# reaction_wheel_board_CURRENT.net
KiCad netlist of a schematic drawn in EAGLE
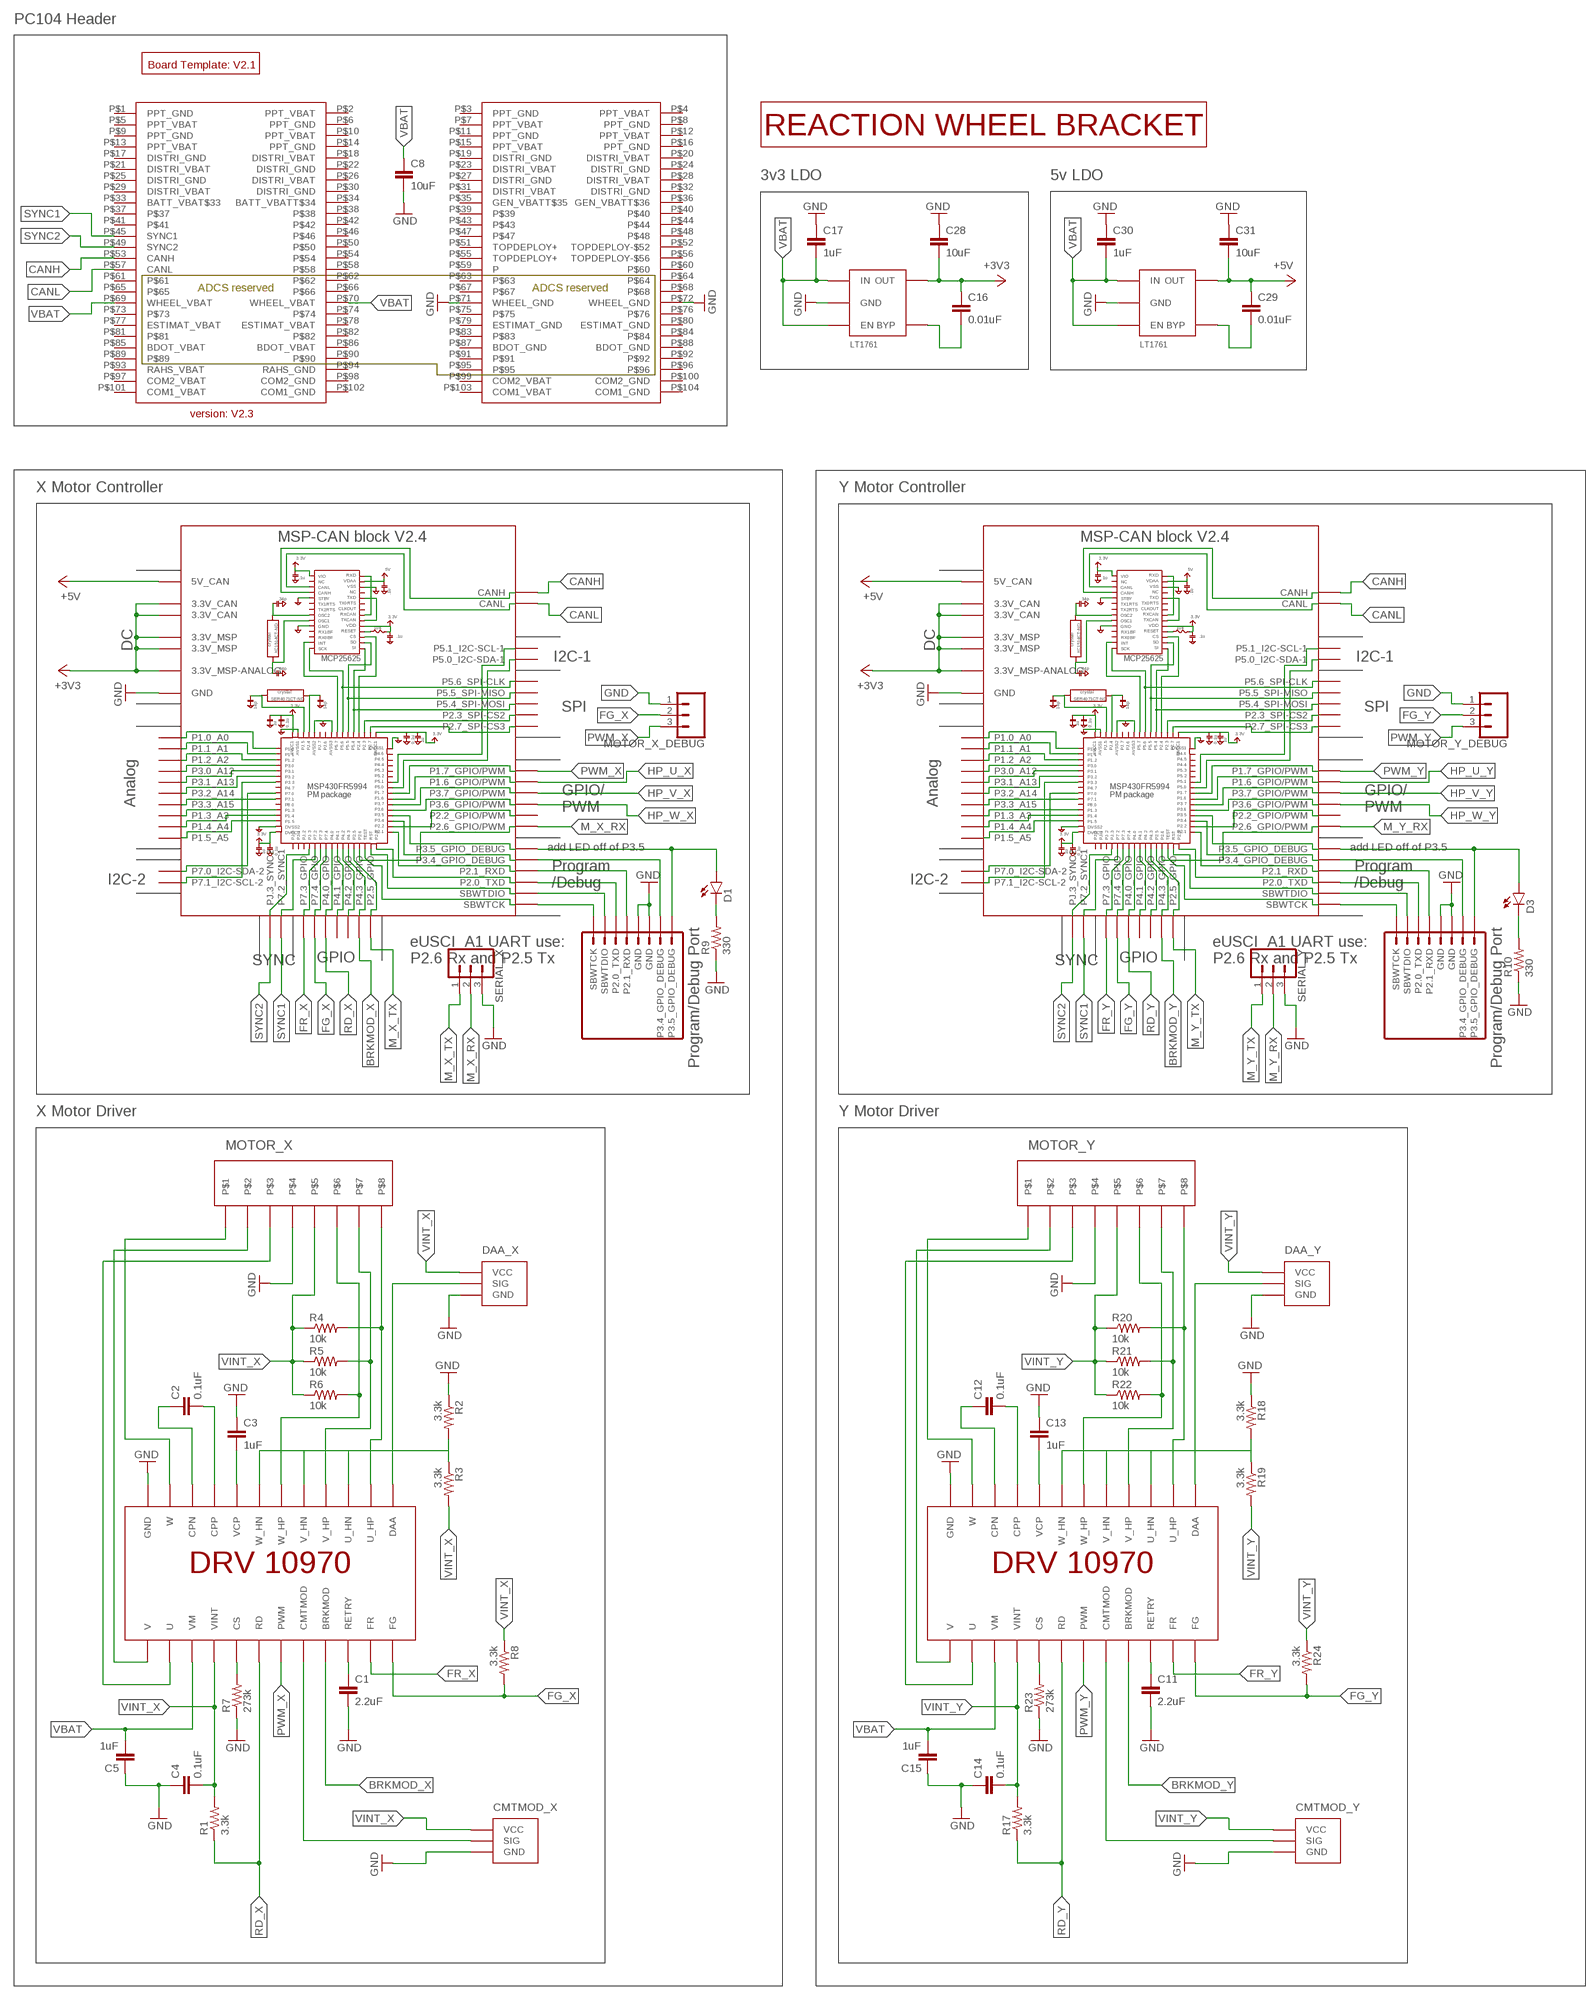
[diagram p0: schematic, sheet 1, part 1 of 2]
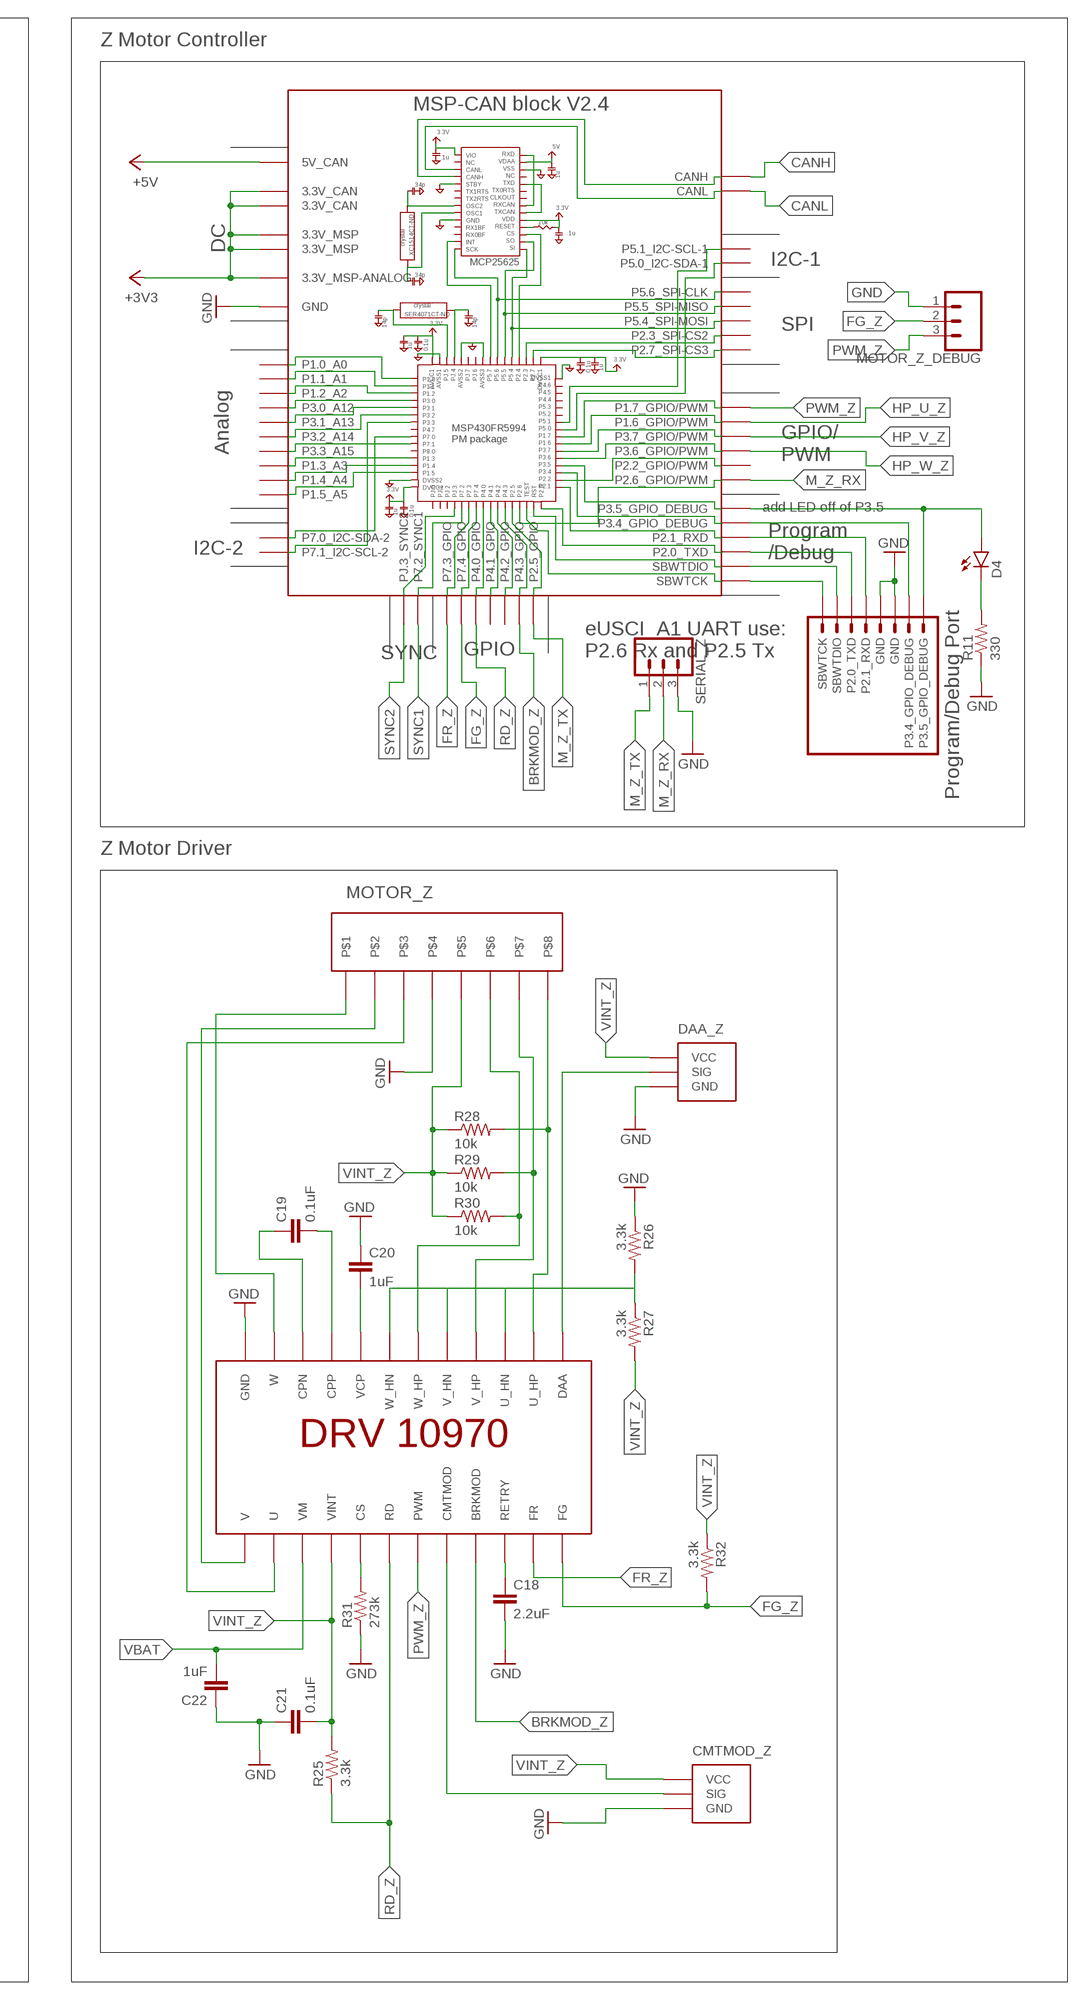
[diagram p1: schematic, sheet 1, part 2 of 2]

(export (version "E")
  (design (tool "Eeschema 10.0.6"))
  (components
    (comp (ref "C1")
      (value "2.2uF")
      (footprint "eagle-import:0805")
      (libsource (lib "eagle-import") (part "CAPACITOR0805"))
    )
    (comp (ref "C2")
      (value "0.1uF")
      (footprint "eagle-import:0805")
      (libsource (lib "eagle-import") (part "CAPACITOR0805"))
    )
    (comp (ref "C3")
      (value "1uF")
      (footprint "eagle-import:0805")
      (libsource (lib "eagle-import") (part "CAPACITOR0805"))
    )
    (comp (ref "C4")
      (value "0.1uF")
      (footprint "eagle-import:0805")
      (libsource (lib "eagle-import") (part "CAPACITOR0805"))
    )
    (comp (ref "C5")
      (value "1uF")
      (footprint "eagle-import:0805")
      (libsource (lib "eagle-import") (part "CAPACITOR0805"))
    )
    (comp (ref "C8")
      (value "10uF")
      (footprint "eagle-import:0805")
      (libsource (lib "eagle-import") (part "CAPACITOR0805"))
    )
    (comp (ref "C11")
      (value "2.2uF")
      (footprint "eagle-import:0805")
      (libsource (lib "eagle-import") (part "CAPACITOR0805"))
    )
    (comp (ref "C12")
      (value "0.1uF")
      (footprint "eagle-import:0805")
      (libsource (lib "eagle-import") (part "CAPACITOR0805"))
    )
    (comp (ref "C13")
      (value "1uF")
      (footprint "eagle-import:0805")
      (libsource (lib "eagle-import") (part "CAPACITOR0805"))
    )
    (comp (ref "C14")
      (value "0.1uF")
      (footprint "eagle-import:0805")
      (libsource (lib "eagle-import") (part "CAPACITOR0805"))
    )
    (comp (ref "C15")
      (value "1uF")
      (footprint "eagle-import:0805")
      (libsource (lib "eagle-import") (part "CAPACITOR0805"))
    )
    (comp (ref "C16")
      (value "0.01uF")
      (footprint "eagle-import:0805")
      (libsource (lib "eagle-import") (part "CAPACITOR0805"))
    )
    (comp (ref "C17")
      (value "1uF")
      (footprint "eagle-import:0805")
      (libsource (lib "eagle-import") (part "CAPACITOR0805"))
    )
    (comp (ref "C18")
      (value "2.2uF")
      (footprint "eagle-import:0805")
      (libsource (lib "eagle-import") (part "CAPACITOR0805"))
    )
    (comp (ref "C19")
      (value "0.1uF")
      (footprint "eagle-import:0805")
      (libsource (lib "eagle-import") (part "CAPACITOR0805"))
    )
    (comp (ref "C20")
      (value "1uF")
      (footprint "eagle-import:0805")
      (libsource (lib "eagle-import") (part "CAPACITOR0805"))
    )
    (comp (ref "C21")
      (value "0.1uF")
      (footprint "eagle-import:0805")
      (libsource (lib "eagle-import") (part "CAPACITOR0805"))
    )
    (comp (ref "C22")
      (value "1uF")
      (footprint "eagle-import:0805")
      (libsource (lib "eagle-import") (part "CAPACITOR0805"))
    )
    (comp (ref "C28")
      (value "10uF")
      (footprint "eagle-import:0805")
      (libsource (lib "eagle-import") (part "CAPACITOR0805"))
    )
    (comp (ref "C29")
      (value "0.01uF")
      (footprint "eagle-import:0805")
      (libsource (lib "eagle-import") (part "CAPACITOR0805"))
    )
    (comp (ref "C30")
      (value "1uF")
      (footprint "eagle-import:0805")
      (libsource (lib "eagle-import") (part "CAPACITOR0805"))
    )
    (comp (ref "C31")
      (value "10uF")
      (footprint "eagle-import:0805")
      (libsource (lib "eagle-import") (part "CAPACITOR0805"))
    )
    (comp (ref "CMTMOD_X")
      (value "0_OHM_JUMPER")
      (footprint "eagle-import:0_OHM_JUMPER")
      (libsource (lib "eagle-import") (part "0_OHM_JUMPER"))
    )
    (comp (ref "CMTMOD_Y")
      (value "0_OHM_JUMPER")
      (footprint "eagle-import:0_OHM_JUMPER")
      (libsource (lib "eagle-import") (part "0_OHM_JUMPER"))
    )
    (comp (ref "CMTMOD_Z")
      (value "0_OHM_JUMPER")
      (footprint "eagle-import:0_OHM_JUMPER")
      (libsource (lib "eagle-import") (part "0_OHM_JUMPER"))
    )
    (comp (ref "D1")
      (value "LED")
      (footprint "eagle-import:LED-1206")
      (libsource (lib "eagle-import") (part "LED"))
    )
    (comp (ref "D3")
      (value "LED")
      (footprint "eagle-import:LED-1206")
      (libsource (lib "eagle-import") (part "LED"))
    )
    (comp (ref "D4")
      (value "LED")
      (footprint "eagle-import:LED-1206")
      (libsource (lib "eagle-import") (part "LED"))
    )
    (comp (ref "DAA_X")
      (value "0_OHM_JUMPER")
      (footprint "eagle-import:0_OHM_JUMPER")
      (libsource (lib "eagle-import") (part "0_OHM_JUMPER"))
    )
    (comp (ref "DAA_Y")
      (value "0_OHM_JUMPER")
      (footprint "eagle-import:0_OHM_JUMPER")
      (libsource (lib "eagle-import") (part "0_OHM_JUMPER"))
    )
    (comp (ref "DAA_Z")
      (value "0_OHM_JUMPER")
      (footprint "eagle-import:0_OHM_JUMPER")
      (libsource (lib "eagle-import") (part "0_OHM_JUMPER"))
    )
    (comp (ref "MOTOR_X")
      (value "PICOLOCK_8")
      (footprint "eagle-import:PICOLOCK_8")
      (libsource (lib "eagle-import") (part "PICOLOCK_8"))
    )
    (comp (ref "MOTOR_X_DEBUG")
      (value "CONN_03LOCK")
      (footprint "eagle-import:1X03_LOCK")
      (libsource (lib "eagle-import") (part "CONN_03LOCK"))
    )
    (comp (ref "MOTOR_Y")
      (value "PICOLOCK_8")
      (footprint "eagle-import:PICOLOCK_8")
      (libsource (lib "eagle-import") (part "PICOLOCK_8"))
    )
    (comp (ref "MOTOR_Y_DEBUG")
      (value "CONN_03LOCK")
      (footprint "eagle-import:1X03_LOCK")
      (libsource (lib "eagle-import") (part "CONN_03LOCK"))
    )
    (comp (ref "MOTOR_Z")
      (value "PICOLOCK_8")
      (footprint "eagle-import:PICOLOCK_8")
      (libsource (lib "eagle-import") (part "PICOLOCK_8"))
    )
    (comp (ref "MOTOR_Z_DEBUG")
      (value "CONN_03LOCK")
      (footprint "eagle-import:1X03_LOCK")
      (libsource (lib "eagle-import") (part "CONN_03LOCK"))
    )
    (comp (ref "MSP_X_DEBUG")
      (value "PROGRAM/DEBUG_PORT")
      (footprint "eagle-import:1X08_CONNECTOR")
      (libsource (lib "eagle-import") (part "PROGRAM/DEBUG_PORT"))
    )
    (comp (ref "MSP_Y_DEBUG")
      (value "PROGRAM/DEBUG_PORT")
      (footprint "eagle-import:1X08_CONNECTOR")
      (libsource (lib "eagle-import") (part "PROGRAM/DEBUG_PORT"))
    )
    (comp (ref "MSP_Z_DEBUG")
      (value "PROGRAM/DEBUG_PORT")
      (footprint "eagle-import:1X08_CONNECTOR")
      (libsource (lib "eagle-import") (part "PROGRAM/DEBUG_PORT"))
    )
    (comp (ref "PC104")
      (value "PC104_CONNECTOR")
      (footprint "eagle-import:PC104_CONNECTOR")
      (libsource (lib "eagle-import") (part "PC104_CONNECTOR"))
    )
    (comp (ref "R1")
      (value "3.3k")
      (footprint "eagle-import:0805")
      (libsource (lib "eagle-import") (part "RESISTOR0805"))
    )
    (comp (ref "R2")
      (value "3.3k")
      (footprint "eagle-import:0805")
      (libsource (lib "eagle-import") (part "RESISTOR0805"))
    )
    (comp (ref "R3")
      (value "3.3k")
      (footprint "eagle-import:0805")
      (libsource (lib "eagle-import") (part "RESISTOR0805"))
    )
    (comp (ref "R4")
      (value "10k")
      (footprint "eagle-import:0805")
      (libsource (lib "eagle-import") (part "RESISTOR0805"))
    )
    (comp (ref "R5")
      (value "10k")
      (footprint "eagle-import:0805")
      (libsource (lib "eagle-import") (part "RESISTOR0805"))
    )
    (comp (ref "R6")
      (value "10k")
      (footprint "eagle-import:0805")
      (libsource (lib "eagle-import") (part "RESISTOR0805"))
    )
    (comp (ref "R7")
      (value "273k")
      (footprint "eagle-import:0805")
      (libsource (lib "eagle-import") (part "RESISTOR0805"))
    )
    (comp (ref "R8")
      (value "3.3k")
      (footprint "eagle-import:0805")
      (libsource (lib "eagle-import") (part "RESISTOR0805"))
    )
    (comp (ref "R9")
      (value "330")
      (footprint "eagle-import:0805")
      (libsource (lib "eagle-import") (part "RESISTOR0805"))
    )
    (comp (ref "R10")
      (value "330")
      (footprint "eagle-import:0805")
      (libsource (lib "eagle-import") (part "RESISTOR0805"))
    )
    (comp (ref "R11")
      (value "330")
      (footprint "eagle-import:0805")
      (libsource (lib "eagle-import") (part "RESISTOR0805"))
    )
    (comp (ref "R17")
      (value "3.3k")
      (footprint "eagle-import:0805")
      (libsource (lib "eagle-import") (part "RESISTOR0805"))
    )
    (comp (ref "R18")
      (value "3.3k")
      (footprint "eagle-import:0805")
      (libsource (lib "eagle-import") (part "RESISTOR0805"))
    )
    (comp (ref "R19")
      (value "3.3k")
      (footprint "eagle-import:0805")
      (libsource (lib "eagle-import") (part "RESISTOR0805"))
    )
    (comp (ref "R20")
      (value "10k")
      (footprint "eagle-import:0805")
      (libsource (lib "eagle-import") (part "RESISTOR0805"))
    )
    (comp (ref "R21")
      (value "10k")
      (footprint "eagle-import:0805")
      (libsource (lib "eagle-import") (part "RESISTOR0805"))
    )
    (comp (ref "R22")
      (value "10k")
      (footprint "eagle-import:0805")
      (libsource (lib "eagle-import") (part "RESISTOR0805"))
    )
    (comp (ref "R23")
      (value "273k")
      (footprint "eagle-import:0805")
      (libsource (lib "eagle-import") (part "RESISTOR0805"))
    )
    (comp (ref "R24")
      (value "3.3k")
      (footprint "eagle-import:0805")
      (libsource (lib "eagle-import") (part "RESISTOR0805"))
    )
    (comp (ref "R25")
      (value "3.3k")
      (footprint "eagle-import:0805")
      (libsource (lib "eagle-import") (part "RESISTOR0805"))
    )
    (comp (ref "R26")
      (value "3.3k")
      (footprint "eagle-import:0805")
      (libsource (lib "eagle-import") (part "RESISTOR0805"))
    )
    (comp (ref "R27")
      (value "3.3k")
      (footprint "eagle-import:0805")
      (libsource (lib "eagle-import") (part "RESISTOR0805"))
    )
    (comp (ref "R28")
      (value "10k")
      (footprint "eagle-import:0805")
      (libsource (lib "eagle-import") (part "RESISTOR0805"))
    )
    (comp (ref "R29")
      (value "10k")
      (footprint "eagle-import:0805")
      (libsource (lib "eagle-import") (part "RESISTOR0805"))
    )
    (comp (ref "R30")
      (value "10k")
      (footprint "eagle-import:0805")
      (libsource (lib "eagle-import") (part "RESISTOR0805"))
    )
    (comp (ref "R31")
      (value "273k")
      (footprint "eagle-import:0805")
      (libsource (lib "eagle-import") (part "RESISTOR0805"))
    )
    (comp (ref "R32")
      (value "3.3k")
      (footprint "eagle-import:0805")
      (libsource (lib "eagle-import") (part "RESISTOR0805"))
    )
    (comp (ref "SERIAL_X")
      (value "CONN_03LOCK")
      (footprint "eagle-import:1X03_LOCK")
      (libsource (lib "eagle-import") (part "CONN_03LOCK"))
    )
    (comp (ref "SERIAL_Y")
      (value "CONN_03LOCK")
      (footprint "eagle-import:1X03_LOCK")
      (libsource (lib "eagle-import") (part "CONN_03LOCK"))
    )
    (comp (ref "SERIAL_Z")
      (value "CONN_03LOCK")
      (footprint "eagle-import:1X03_LOCK")
      (libsource (lib "eagle-import") (part "CONN_03LOCK"))
    )
    (comp (ref "U$1")
      (value "BOARD_TEMPLATESERCURED")
      (footprint "eagle-import:BOARD_TEMPLATE_SECURED")
      (libsource (lib "eagle-import") (part "BOARD_TEMPLATESERCURED"))
    )
    (comp (ref "U$3")
      (value "MSP-CAN_BLOCK")
      (footprint "eagle-import:MSP-CAN_BLOCK")
      (libsource (lib "eagle-import") (part "MSP-CAN_BLOCK"))
    )
    (comp (ref "U$7")
      (value "DRV10970")
      (footprint "eagle-import:DRV10970")
      (libsource (lib "eagle-import") (part "DRV10970"))
    )
    (comp (ref "U$9")
      (value "REACTION_WHEEL_BRACKET")
      (footprint "eagle-import:REACTION_WHEEL_BRACKET")
      (libsource (lib "eagle-import") (part "REACTION_WHEEL_BRACKET"))
    )
    (comp (ref "U$10")
      (value "MSP-CAN_BLOCK")
      (footprint "eagle-import:MSP-CAN_BLOCK")
      (libsource (lib "eagle-import") (part "MSP-CAN_BLOCK"))
    )
    (comp (ref "U$12")
      (value "DRV10970")
      (footprint "eagle-import:DRV10970")
      (libsource (lib "eagle-import") (part "DRV10970"))
    )
    (comp (ref "U$13")
      (value "MSP-CAN_BLOCK")
      (footprint "eagle-import:MSP-CAN_BLOCK")
      (libsource (lib "eagle-import") (part "MSP-CAN_BLOCK"))
    )
    (comp (ref "U$15")
      (value "DRV10970")
      (footprint "eagle-import:DRV10970")
      (libsource (lib "eagle-import") (part "DRV10970"))
    )
    (comp (ref "U2")
      (value "LT1761-X")
      (footprint "eagle-import:SOT-23-5")
      (libsource (lib "eagle-import") (part "LT1761-X"))
    )
    (comp (ref "U3")
      (value "LT1761-X")
      (footprint "eagle-import:SOT-23-5")
      (libsource (lib "eagle-import") (part "LT1761-X"))
    )
  )
  (nets
    (net (code "1") (name "+3V3") (class "Default")
      (node (ref "C16") (pin "1") (pinfunction "1_1") (pintype "passive"))
      (node (ref "C28") (pin "2") (pinfunction "2_2") (pintype "passive"))
      (node (ref "U$10") (pin "3.3V@CAN1") (pinfunction "3.3V_CAN_3.3V@CAN1") (pintype "bidirectional"))
      (node (ref "U$10") (pin "3.3V@CAN2") (pinfunction "3.3V_CAN_3.3V@CAN2") (pintype "bidirectional"))
      (node (ref "U$10") (pin "3.3V@MSP1") (pinfunction "3.3V_MSP_3.3V@MSP1") (pintype "bidirectional"))
      (node (ref "U$10") (pin "3.3V@MSP2") (pinfunction "3.3V_MSP_3.3V@MSP2") (pintype "bidirectional"))
      (node (ref "U$10") (pin "3.3V_ANALOG@MSP2") (pinfunction "3.3V_MSP-ANALOG_3.3V_ANALOG@MSP2") (pintype "bidirectional"))
      (node (ref "U$13") (pin "3.3V@CAN1") (pinfunction "3.3V_CAN_3.3V@CAN1") (pintype "bidirectional"))
      (node (ref "U$13") (pin "3.3V@CAN2") (pinfunction "3.3V_CAN_3.3V@CAN2") (pintype "bidirectional"))
      (node (ref "U$13") (pin "3.3V@MSP1") (pinfunction "3.3V_MSP_3.3V@MSP1") (pintype "bidirectional"))
      (node (ref "U$13") (pin "3.3V@MSP2") (pinfunction "3.3V_MSP_3.3V@MSP2") (pintype "bidirectional"))
      (node (ref "U$13") (pin "3.3V_ANALOG@MSP2") (pinfunction "3.3V_MSP-ANALOG_3.3V_ANALOG@MSP2") (pintype "bidirectional"))
      (node (ref "U$3") (pin "3.3V@CAN1") (pinfunction "3.3V_CAN_3.3V@CAN1") (pintype "bidirectional"))
      (node (ref "U$3") (pin "3.3V@CAN2") (pinfunction "3.3V_CAN_3.3V@CAN2") (pintype "bidirectional"))
      (node (ref "U$3") (pin "3.3V@MSP1") (pinfunction "3.3V_MSP_3.3V@MSP1") (pintype "bidirectional"))
      (node (ref "U$3") (pin "3.3V@MSP2") (pinfunction "3.3V_MSP_3.3V@MSP2") (pintype "bidirectional"))
      (node (ref "U$3") (pin "3.3V_ANALOG@MSP2") (pinfunction "3.3V_MSP-ANALOG_3.3V_ANALOG@MSP2") (pintype "bidirectional"))
      (node (ref "U2") (pin "P$5") (pinfunction "OUT_P$5") (pintype "bidirectional"))
    )
    (net (code "2") (name "+5V") (class "Default")
      (node (ref "C29") (pin "1") (pinfunction "1_1") (pintype "passive"))
      (node (ref "C31") (pin "2") (pinfunction "2_2") (pintype "passive"))
      (node (ref "U$10") (pin "5V") (pinfunction "5V_CAN_5V") (pintype "bidirectional"))
      (node (ref "U$13") (pin "5V") (pinfunction "5V_CAN_5V") (pintype "bidirectional"))
      (node (ref "U$3") (pin "5V") (pinfunction "5V_CAN_5V") (pintype "bidirectional"))
      (node (ref "U3") (pin "P$5") (pinfunction "OUT_P$5") (pintype "bidirectional"))
    )
    (net (code "3") (name "BRKMOD_X") (class "Default")
      (node (ref "U$3") (pin "P4.3_GPIO") (pinfunction "P4.3_GPIO_P4.3_GPIO") (pintype "bidirectional"))
      (node (ref "U$7") (pin "BRKMOD") (pinfunction "BRKMOD_BRKMOD") (pintype "bidirectional"))
    )
    (net (code "4") (name "BRKMOD_Y") (class "Default")
      (node (ref "U$10") (pin "P4.3_GPIO") (pinfunction "P4.3_GPIO_P4.3_GPIO") (pintype "bidirectional"))
      (node (ref "U$12") (pin "BRKMOD") (pinfunction "BRKMOD_BRKMOD") (pintype "bidirectional"))
    )
    (net (code "5") (name "BRKMOD_Z") (class "Default")
      (node (ref "U$13") (pin "P4.3_GPIO") (pinfunction "P4.3_GPIO_P4.3_GPIO") (pintype "bidirectional"))
      (node (ref "U$15") (pin "BRKMOD") (pinfunction "BRKMOD_BRKMOD") (pintype "bidirectional"))
    )
    (net (code "6") (name "CANH") (class "Default")
      (node (ref "PC104") (pin "P$53") (pinfunction "CANH_P$53") (pintype "bidirectional"))
      (node (ref "U$10") (pin "CANH") (pinfunction "CANH_CANH") (pintype "bidirectional"))
      (node (ref "U$13") (pin "CANH") (pinfunction "CANH_CANH") (pintype "bidirectional"))
      (node (ref "U$3") (pin "CANH") (pinfunction "CANH_CANH") (pintype "bidirectional"))
    )
    (net (code "7") (name "CANL") (class "Default")
      (node (ref "PC104") (pin "P$57") (pinfunction "CANL_P$57") (pintype "bidirectional"))
      (node (ref "U$10") (pin "CANL") (pinfunction "CANL_CANL") (pintype "bidirectional"))
      (node (ref "U$13") (pin "CANL") (pinfunction "CANL_CANL") (pintype "bidirectional"))
      (node (ref "U$3") (pin "CANL") (pinfunction "CANL_CANL") (pintype "bidirectional"))
    )
    (net (code "8") (name "FG_X") (class "Default")
      (node (ref "MOTOR_X_DEBUG") (pin "2") (pinfunction "2_2") (pintype "passive"))
      (node (ref "R8") (pin "2") (pinfunction "2_2") (pintype "passive"))
      (node (ref "U$3") (pin "P7.4_GPIO") (pinfunction "P7.4_GPIO_P7.4_GPIO") (pintype "bidirectional"))
      (node (ref "U$7") (pin "FG") (pinfunction "FG_FG") (pintype "bidirectional"))
    )
    (net (code "9") (name "FG_Y") (class "Default")
      (node (ref "MOTOR_Y_DEBUG") (pin "2") (pinfunction "2_2") (pintype "passive"))
      (node (ref "R24") (pin "2") (pinfunction "2_2") (pintype "passive"))
      (node (ref "U$10") (pin "P7.4_GPIO") (pinfunction "P7.4_GPIO_P7.4_GPIO") (pintype "bidirectional"))
      (node (ref "U$12") (pin "FG") (pinfunction "FG_FG") (pintype "bidirectional"))
    )
    (net (code "10") (name "FG_Z") (class "Default")
      (node (ref "MOTOR_Z_DEBUG") (pin "2") (pinfunction "2_2") (pintype "passive"))
      (node (ref "R32") (pin "2") (pinfunction "2_2") (pintype "passive"))
      (node (ref "U$13") (pin "P7.4_GPIO") (pinfunction "P7.4_GPIO_P7.4_GPIO") (pintype "bidirectional"))
      (node (ref "U$15") (pin "FG") (pinfunction "FG_FG") (pintype "bidirectional"))
    )
    (net (code "11") (name "FR_X") (class "Default")
      (node (ref "U$3") (pin "P7.3_GPIO") (pinfunction "P7.3_GPIO_P7.3_GPIO") (pintype "bidirectional"))
      (node (ref "U$7") (pin "FR") (pinfunction "FR_FR") (pintype "bidirectional"))
    )
    (net (code "12") (name "FR_Y") (class "Default")
      (node (ref "U$10") (pin "P7.3_GPIO") (pinfunction "P7.3_GPIO_P7.3_GPIO") (pintype "bidirectional"))
      (node (ref "U$12") (pin "FR") (pinfunction "FR_FR") (pintype "bidirectional"))
    )
    (net (code "13") (name "FR_Z") (class "Default")
      (node (ref "U$13") (pin "P7.3_GPIO") (pinfunction "P7.3_GPIO_P7.3_GPIO") (pintype "bidirectional"))
      (node (ref "U$15") (pin "FR") (pinfunction "FR_FR") (pintype "bidirectional"))
    )
    (net (code "14") (name "GND") (class "Default")
      (node (ref "C1") (pin "2") (pinfunction "2_2") (pintype "passive"))
      (node (ref "C11") (pin "2") (pinfunction "2_2") (pintype "passive"))
      (node (ref "C13") (pin "1") (pinfunction "1_1") (pintype "passive"))
      (node (ref "C14") (pin "1") (pinfunction "1_1") (pintype "passive"))
      (node (ref "C15") (pin "1") (pinfunction "1_1") (pintype "passive"))
      (node (ref "C17") (pin "1") (pinfunction "1_1") (pintype "passive"))
      (node (ref "C18") (pin "2") (pinfunction "2_2") (pintype "passive"))
      (node (ref "C20") (pin "1") (pinfunction "1_1") (pintype "passive"))
      (node (ref "C21") (pin "1") (pinfunction "1_1") (pintype "passive"))
      (node (ref "C22") (pin "1") (pinfunction "1_1") (pintype "passive"))
      (node (ref "C28") (pin "1") (pinfunction "1_1") (pintype "passive"))
      (node (ref "C3") (pin "1") (pinfunction "1_1") (pintype "passive"))
      (node (ref "C30") (pin "1") (pinfunction "1_1") (pintype "passive"))
      (node (ref "C31") (pin "1") (pinfunction "1_1") (pintype "passive"))
      (node (ref "C4") (pin "1") (pinfunction "1_1") (pintype "passive"))
      (node (ref "C5") (pin "1") (pinfunction "1_1") (pintype "passive"))
      (node (ref "C8") (pin "2") (pinfunction "2_2") (pintype "passive"))
      (node (ref "CMTMOD_X") (pin "P$1") (pinfunction "GND_P$1") (pintype "bidirectional"))
      (node (ref "CMTMOD_Y") (pin "P$1") (pinfunction "GND_P$1") (pintype "bidirectional"))
      (node (ref "CMTMOD_Z") (pin "P$1") (pinfunction "GND_P$1") (pintype "bidirectional"))
      (node (ref "DAA_X") (pin "P$1") (pinfunction "GND_P$1") (pintype "bidirectional"))
      (node (ref "DAA_Y") (pin "P$1") (pinfunction "GND_P$1") (pintype "bidirectional"))
      (node (ref "DAA_Z") (pin "P$1") (pinfunction "GND_P$1") (pintype "bidirectional"))
      (node (ref "MOTOR_X") (pin "P$4") (pinfunction "P$4_P$4") (pintype "bidirectional"))
      (node (ref "MOTOR_X_DEBUG") (pin "1") (pinfunction "1_1") (pintype "passive"))
      (node (ref "MOTOR_Y") (pin "P$4") (pinfunction "P$4_P$4") (pintype "bidirectional"))
      (node (ref "MOTOR_Y_DEBUG") (pin "1") (pinfunction "1_1") (pintype "passive"))
      (node (ref "MOTOR_Z") (pin "P$4") (pinfunction "P$4_P$4") (pintype "bidirectional"))
      (node (ref "MOTOR_Z_DEBUG") (pin "1") (pinfunction "1_1") (pintype "passive"))
      (node (ref "MSP_X_DEBUG") (pin "5") (pinfunction "GND_5") (pintype "bidirectional"))
      (node (ref "MSP_X_DEBUG") (pin "6") (pinfunction "GND_6") (pintype "bidirectional"))
      (node (ref "MSP_Y_DEBUG") (pin "5") (pinfunction "GND_5") (pintype "bidirectional"))
      (node (ref "MSP_Y_DEBUG") (pin "6") (pinfunction "GND_6") (pintype "bidirectional"))
      (node (ref "MSP_Z_DEBUG") (pin "5") (pinfunction "GND_5") (pintype "bidirectional"))
      (node (ref "MSP_Z_DEBUG") (pin "6") (pinfunction "GND_6") (pintype "bidirectional"))
      (node (ref "PC104") (pin "P$71") (pinfunction "WHEEL_GND_P$71") (pintype "bidirectional"))
      (node (ref "PC104") (pin "P$72") (pinfunction "WHEEL_GND_P$72") (pintype "bidirectional"))
      (node (ref "R10") (pin "1") (pinfunction "1_1") (pintype "passive"))
      (node (ref "R11") (pin "1") (pinfunction "1_1") (pintype "passive"))
      (node (ref "R18") (pin "1") (pinfunction "1_1") (pintype "passive"))
      (node (ref "R2") (pin "1") (pinfunction "1_1") (pintype "passive"))
      (node (ref "R23") (pin "1") (pinfunction "1_1") (pintype "passive"))
      (node (ref "R26") (pin "1") (pinfunction "1_1") (pintype "passive"))
      (node (ref "R31") (pin "1") (pinfunction "1_1") (pintype "passive"))
      (node (ref "R7") (pin "1") (pinfunction "1_1") (pintype "passive"))
      (node (ref "R9") (pin "1") (pinfunction "1_1") (pintype "passive"))
      (node (ref "SERIAL_X") (pin "3") (pinfunction "3_3") (pintype "passive"))
      (node (ref "SERIAL_Y") (pin "3") (pinfunction "3_3") (pintype "passive"))
      (node (ref "SERIAL_Z") (pin "3") (pinfunction "3_3") (pintype "passive"))
      (node (ref "U$10") (pin "GND@1") (pinfunction "GND_GND@1") (pintype "bidirectional"))
      (node (ref "U$10") (pin "GND@10") (pinfunction "GND_GND@10") (pintype "bidirectional"))
      (node (ref "U$10") (pin "GND@11") (pinfunction "GND_GND@11") (pintype "bidirectional"))
      (node (ref "U$10") (pin "GND@12") (pinfunction "GND_GND@12") (pintype "bidirectional"))
      (node (ref "U$10") (pin "GND@13") (pinfunction "GND_GND@13") (pintype "bidirectional"))
      (node (ref "U$10") (pin "GND@14") (pinfunction "GND_GND@14") (pintype "bidirectional"))
      (node (ref "U$10") (pin "GND@15") (pinfunction "GND_GND@15") (pintype "bidirectional"))
      (node (ref "U$10") (pin "GND@16") (pinfunction "GND_GND@16") (pintype "bidirectional"))
      (node (ref "U$10") (pin "GND@17") (pinfunction "GND_GND@17") (pintype "bidirectional"))
      (node (ref "U$10") (pin "GND@2") (pinfunction "GND_GND@2") (pintype "bidirectional"))
      (node (ref "U$10") (pin "GND@26") (pinfunction "GND_GND@26") (pintype "bidirectional"))
      (node (ref "U$10") (pin "GND@3") (pinfunction "GND_GND@3") (pintype "bidirectional"))
      (node (ref "U$10") (pin "GND@4") (pinfunction "GND_GND@4") (pintype "bidirectional"))
      (node (ref "U$10") (pin "GND@5") (pinfunction "GND_GND@5") (pintype "bidirectional"))
      (node (ref "U$10") (pin "GND@7") (pinfunction "GND_GND@7") (pintype "bidirectional"))
      (node (ref "U$10") (pin "GND@8") (pinfunction "GND_GND@8") (pintype "bidirectional"))
      (node (ref "U$10") (pin "GND@9") (pinfunction "GND_GND@9") (pintype "bidirectional"))
      (node (ref "U$12") (pin "GND@1") (pinfunction "GND_GND@1") (pintype "bidirectional"))
      (node (ref "U$12") (pin "GND@2") (pinfunction "GND_GND@2") (pintype "bidirectional"))
      (node (ref "U$13") (pin "GND@1") (pinfunction "GND_GND@1") (pintype "bidirectional"))
      (node (ref "U$13") (pin "GND@10") (pinfunction "GND_GND@10") (pintype "bidirectional"))
      (node (ref "U$13") (pin "GND@11") (pinfunction "GND_GND@11") (pintype "bidirectional"))
      (node (ref "U$13") (pin "GND@12") (pinfunction "GND_GND@12") (pintype "bidirectional"))
      (node (ref "U$13") (pin "GND@13") (pinfunction "GND_GND@13") (pintype "bidirectional"))
      (node (ref "U$13") (pin "GND@14") (pinfunction "GND_GND@14") (pintype "bidirectional"))
      (node (ref "U$13") (pin "GND@15") (pinfunction "GND_GND@15") (pintype "bidirectional"))
      (node (ref "U$13") (pin "GND@16") (pinfunction "GND_GND@16") (pintype "bidirectional"))
      (node (ref "U$13") (pin "GND@17") (pinfunction "GND_GND@17") (pintype "bidirectional"))
      (node (ref "U$13") (pin "GND@2") (pinfunction "GND_GND@2") (pintype "bidirectional"))
      (node (ref "U$13") (pin "GND@26") (pinfunction "GND_GND@26") (pintype "bidirectional"))
      (node (ref "U$13") (pin "GND@3") (pinfunction "GND_GND@3") (pintype "bidirectional"))
      (node (ref "U$13") (pin "GND@4") (pinfunction "GND_GND@4") (pintype "bidirectional"))
      (node (ref "U$13") (pin "GND@5") (pinfunction "GND_GND@5") (pintype "bidirectional"))
      (node (ref "U$13") (pin "GND@7") (pinfunction "GND_GND@7") (pintype "bidirectional"))
      (node (ref "U$13") (pin "GND@8") (pinfunction "GND_GND@8") (pintype "bidirectional"))
      (node (ref "U$13") (pin "GND@9") (pinfunction "GND_GND@9") (pintype "bidirectional"))
      (node (ref "U$15") (pin "GND@1") (pinfunction "GND_GND@1") (pintype "bidirectional"))
      (node (ref "U$15") (pin "GND@2") (pinfunction "GND_GND@2") (pintype "bidirectional"))
      (node (ref "U$3") (pin "GND@1") (pinfunction "GND_GND@1") (pintype "bidirectional"))
      (node (ref "U$3") (pin "GND@10") (pinfunction "GND_GND@10") (pintype "bidirectional"))
      (node (ref "U$3") (pin "GND@11") (pinfunction "GND_GND@11") (pintype "bidirectional"))
      (node (ref "U$3") (pin "GND@12") (pinfunction "GND_GND@12") (pintype "bidirectional"))
      (node (ref "U$3") (pin "GND@13") (pinfunction "GND_GND@13") (pintype "bidirectional"))
      (node (ref "U$3") (pin "GND@14") (pinfunction "GND_GND@14") (pintype "bidirectional"))
      (node (ref "U$3") (pin "GND@15") (pinfunction "GND_GND@15") (pintype "bidirectional"))
      (node (ref "U$3") (pin "GND@16") (pinfunction "GND_GND@16") (pintype "bidirectional"))
      (node (ref "U$3") (pin "GND@17") (pinfunction "GND_GND@17") (pintype "bidirectional"))
      (node (ref "U$3") (pin "GND@2") (pinfunction "GND_GND@2") (pintype "bidirectional"))
      (node (ref "U$3") (pin "GND@26") (pinfunction "GND_GND@26") (pintype "bidirectional"))
      (node (ref "U$3") (pin "GND@3") (pinfunction "GND_GND@3") (pintype "bidirectional"))
      (node (ref "U$3") (pin "GND@4") (pinfunction "GND_GND@4") (pintype "bidirectional"))
      (node (ref "U$3") (pin "GND@5") (pinfunction "GND_GND@5") (pintype "bidirectional"))
      (node (ref "U$3") (pin "GND@7") (pinfunction "GND_GND@7") (pintype "bidirectional"))
      (node (ref "U$3") (pin "GND@8") (pinfunction "GND_GND@8") (pintype "bidirectional"))
      (node (ref "U$3") (pin "GND@9") (pinfunction "GND_GND@9") (pintype "bidirectional"))
      (node (ref "U$7") (pin "GND@1") (pinfunction "GND_GND@1") (pintype "bidirectional"))
      (node (ref "U$7") (pin "GND@2") (pinfunction "GND_GND@2") (pintype "bidirectional"))
      (node (ref "U2") (pin "P$2") (pinfunction "GND_P$2") (pintype "bidirectional"))
      (node (ref "U3") (pin "P$2") (pinfunction "GND_P$2") (pintype "bidirectional"))
    )
    (net (code "15") (name "HP_U_X") (class "Default")
      (node (ref "MOTOR_X") (pin "P$8") (pinfunction "P$8_P$8") (pintype "bidirectional"))
      (node (ref "R4") (pin "2") (pinfunction "2_2") (pintype "passive"))
      (node (ref "U$3") (pin "P1.6_GPIO/PWM") (pinfunction "P1.6_GPIO/PWM_P1.6_GPIO/PWM") (pintype "bidirectional"))
      (node (ref "U$7") (pin "U_HP") (pinfunction "U_HP_U_HP") (pintype "bidirectional"))
    )
    (net (code "16") (name "HP_U_Y") (class "Default")
      (node (ref "MOTOR_Y") (pin "P$8") (pinfunction "P$8_P$8") (pintype "bidirectional"))
      (node (ref "R20") (pin "2") (pinfunction "2_2") (pintype "passive"))
      (node (ref "U$10") (pin "P1.6_GPIO/PWM") (pinfunction "P1.6_GPIO/PWM_P1.6_GPIO/PWM") (pintype "bidirectional"))
      (node (ref "U$12") (pin "U_HP") (pinfunction "U_HP_U_HP") (pintype "bidirectional"))
    )
    (net (code "17") (name "HP_U_Z") (class "Default")
      (node (ref "MOTOR_Z") (pin "P$8") (pinfunction "P$8_P$8") (pintype "bidirectional"))
      (node (ref "R28") (pin "2") (pinfunction "2_2") (pintype "passive"))
      (node (ref "U$13") (pin "P1.6_GPIO/PWM") (pinfunction "P1.6_GPIO/PWM_P1.6_GPIO/PWM") (pintype "bidirectional"))
      (node (ref "U$15") (pin "U_HP") (pinfunction "U_HP_U_HP") (pintype "bidirectional"))
    )
    (net (code "18") (name "HP_V_X") (class "Default")
      (node (ref "MOTOR_X") (pin "P$7") (pinfunction "P$7_P$7") (pintype "bidirectional"))
      (node (ref "R5") (pin "2") (pinfunction "2_2") (pintype "passive"))
      (node (ref "U$3") (pin "P3.7_GPIO/PWM") (pinfunction "P3.7_GPIO/PWM_P3.7_GPIO/PWM") (pintype "bidirectional"))
      (node (ref "U$7") (pin "V_HP") (pinfunction "V_HP_V_HP") (pintype "bidirectional"))
    )
    (net (code "19") (name "HP_V_Y") (class "Default")
      (node (ref "MOTOR_Y") (pin "P$7") (pinfunction "P$7_P$7") (pintype "bidirectional"))
      (node (ref "R21") (pin "2") (pinfunction "2_2") (pintype "passive"))
      (node (ref "U$10") (pin "P3.7_GPIO/PWM") (pinfunction "P3.7_GPIO/PWM_P3.7_GPIO/PWM") (pintype "bidirectional"))
      (node (ref "U$12") (pin "V_HP") (pinfunction "V_HP_V_HP") (pintype "bidirectional"))
    )
    (net (code "20") (name "HP_V_Z") (class "Default")
      (node (ref "MOTOR_Z") (pin "P$7") (pinfunction "P$7_P$7") (pintype "bidirectional"))
      (node (ref "R29") (pin "2") (pinfunction "2_2") (pintype "passive"))
      (node (ref "U$13") (pin "P3.7_GPIO/PWM") (pinfunction "P3.7_GPIO/PWM_P3.7_GPIO/PWM") (pintype "bidirectional"))
      (node (ref "U$15") (pin "V_HP") (pinfunction "V_HP_V_HP") (pintype "bidirectional"))
    )
    (net (code "21") (name "HP_W_X") (class "Default")
      (node (ref "MOTOR_X") (pin "P$6") (pinfunction "P$6_P$6") (pintype "bidirectional"))
      (node (ref "R6") (pin "2") (pinfunction "2_2") (pintype "passive"))
      (node (ref "U$3") (pin "P3.6_GPIO/PWM") (pinfunction "P3.6_GPIO/PWM_P3.6_GPIO/PWM") (pintype "bidirectional"))
      (node (ref "U$7") (pin "W_HP") (pinfunction "W_HP_W_HP") (pintype "bidirectional"))
    )
    (net (code "22") (name "HP_W_Y") (class "Default")
      (node (ref "MOTOR_Y") (pin "P$6") (pinfunction "P$6_P$6") (pintype "bidirectional"))
      (node (ref "R22") (pin "2") (pinfunction "2_2") (pintype "passive"))
      (node (ref "U$10") (pin "P3.6_GPIO/PWM") (pinfunction "P3.6_GPIO/PWM_P3.6_GPIO/PWM") (pintype "bidirectional"))
      (node (ref "U$12") (pin "W_HP") (pinfunction "W_HP_W_HP") (pintype "bidirectional"))
    )
    (net (code "23") (name "HP_W_Z") (class "Default")
      (node (ref "MOTOR_Z") (pin "P$6") (pinfunction "P$6_P$6") (pintype "bidirectional"))
      (node (ref "R30") (pin "2") (pinfunction "2_2") (pintype "passive"))
      (node (ref "U$13") (pin "P3.6_GPIO/PWM") (pinfunction "P3.6_GPIO/PWM_P3.6_GPIO/PWM") (pintype "bidirectional"))
      (node (ref "U$15") (pin "W_HP") (pinfunction "W_HP_W_HP") (pintype "bidirectional"))
    )
    (net (code "24") (name "M_X_RX") (class "Default")
      (node (ref "SERIAL_X") (pin "2") (pinfunction "2_2") (pintype "passive"))
      (node (ref "U$3") (pin "P2.6_GPIO/PWM") (pinfunction "P2.6_GPIO/PWM_P2.6_GPIO/PWM") (pintype "bidirectional"))
    )
    (net (code "25") (name "M_X_TX") (class "Default")
      (node (ref "SERIAL_X") (pin "1") (pinfunction "1_1") (pintype "passive"))
      (node (ref "U$3") (pin "P2.5_GPIO") (pinfunction "P2.5_GPIO_P2.5_GPIO") (pintype "bidirectional"))
    )
    (net (code "26") (name "M_Y_RX") (class "Default")
      (node (ref "SERIAL_Y") (pin "2") (pinfunction "2_2") (pintype "passive"))
      (node (ref "U$10") (pin "P2.6_GPIO/PWM") (pinfunction "P2.6_GPIO/PWM_P2.6_GPIO/PWM") (pintype "bidirectional"))
    )
    (net (code "27") (name "M_Y_TX") (class "Default")
      (node (ref "SERIAL_Y") (pin "1") (pinfunction "1_1") (pintype "passive"))
      (node (ref "U$10") (pin "P2.5_GPIO") (pinfunction "P2.5_GPIO_P2.5_GPIO") (pintype "bidirectional"))
    )
    (net (code "28") (name "M_Z_RX") (class "Default")
      (node (ref "SERIAL_Z") (pin "2") (pinfunction "2_2") (pintype "passive"))
      (node (ref "U$13") (pin "P2.6_GPIO/PWM") (pinfunction "P2.6_GPIO/PWM_P2.6_GPIO/PWM") (pintype "bidirectional"))
    )
    (net (code "29") (name "M_Z_TX") (class "Default")
      (node (ref "SERIAL_Z") (pin "1") (pinfunction "1_1") (pintype "passive"))
      (node (ref "U$13") (pin "P2.5_GPIO") (pinfunction "P2.5_GPIO_P2.5_GPIO") (pintype "bidirectional"))
    )
    (net (code "30") (name "Net-(C1-Pad1)") (class "Default")
      (node (ref "C1") (pin "1") (pinfunction "1_1") (pintype "passive"))
      (node (ref "U$7") (pin "RETRY") (pinfunction "RETRY_RETRY") (pintype "bidirectional"))
    )
    (net (code "31") (name "Net-(C2-Pad1)") (class "Default")
      (node (ref "C2") (pin "1") (pinfunction "1_1") (pintype "passive"))
      (node (ref "U$7") (pin "CPN") (pinfunction "CPN_CPN") (pintype "bidirectional"))
    )
    (net (code "32") (name "Net-(C2-Pad2)") (class "Default")
      (node (ref "C2") (pin "2") (pinfunction "2_2") (pintype "passive"))
      (node (ref "U$7") (pin "CPP") (pinfunction "CPP_CPP") (pintype "bidirectional"))
    )
    (net (code "33") (name "Net-(C3-Pad2)") (class "Default")
      (node (ref "C3") (pin "2") (pinfunction "2_2") (pintype "passive"))
      (node (ref "U$7") (pin "VCP") (pinfunction "VCP_VCP") (pintype "bidirectional"))
    )
    (net (code "34") (name "Net-(C11-Pad1)") (class "Default")
      (node (ref "C11") (pin "1") (pinfunction "1_1") (pintype "passive"))
      (node (ref "U$12") (pin "RETRY") (pinfunction "RETRY_RETRY") (pintype "bidirectional"))
    )
    (net (code "35") (name "Net-(C12-Pad1)") (class "Default")
      (node (ref "C12") (pin "1") (pinfunction "1_1") (pintype "passive"))
      (node (ref "U$12") (pin "CPN") (pinfunction "CPN_CPN") (pintype "bidirectional"))
    )
    (net (code "36") (name "Net-(C12-Pad2)") (class "Default")
      (node (ref "C12") (pin "2") (pinfunction "2_2") (pintype "passive"))
      (node (ref "U$12") (pin "CPP") (pinfunction "CPP_CPP") (pintype "bidirectional"))
    )
    (net (code "37") (name "Net-(C13-Pad2)") (class "Default")
      (node (ref "C13") (pin "2") (pinfunction "2_2") (pintype "passive"))
      (node (ref "U$12") (pin "VCP") (pinfunction "VCP_VCP") (pintype "bidirectional"))
    )
    (net (code "38") (name "Net-(C18-Pad1)") (class "Default")
      (node (ref "C18") (pin "1") (pinfunction "1_1") (pintype "passive"))
      (node (ref "U$15") (pin "RETRY") (pinfunction "RETRY_RETRY") (pintype "bidirectional"))
    )
    (net (code "39") (name "Net-(C19-Pad1)") (class "Default")
      (node (ref "C19") (pin "1") (pinfunction "1_1") (pintype "passive"))
      (node (ref "U$15") (pin "CPN") (pinfunction "CPN_CPN") (pintype "bidirectional"))
    )
    (net (code "40") (name "Net-(C19-Pad2)") (class "Default")
      (node (ref "C19") (pin "2") (pinfunction "2_2") (pintype "passive"))
      (node (ref "U$15") (pin "CPP") (pinfunction "CPP_CPP") (pintype "bidirectional"))
    )
    (net (code "41") (name "Net-(C20-Pad2)") (class "Default")
      (node (ref "C20") (pin "2") (pinfunction "2_2") (pintype "passive"))
      (node (ref "U$15") (pin "VCP") (pinfunction "VCP_VCP") (pintype "bidirectional"))
    )
    (net (code "42") (name "Net-(CMTMOD_X-SIG)") (class "Default")
      (node (ref "CMTMOD_X") (pin "P$2") (pinfunction "SIG_P$2") (pintype "bidirectional"))
      (node (ref "U$7") (pin "CMTMOD") (pinfunction "CMTMOD_CMTMOD") (pintype "bidirectional"))
    )
    (net (code "43") (name "Net-(CMTMOD_Y-SIG)") (class "Default")
      (node (ref "CMTMOD_Y") (pin "P$2") (pinfunction "SIG_P$2") (pintype "bidirectional"))
      (node (ref "U$12") (pin "CMTMOD") (pinfunction "CMTMOD_CMTMOD") (pintype "bidirectional"))
    )
    (net (code "44") (name "Net-(CMTMOD_Z-SIG)") (class "Default")
      (node (ref "CMTMOD_Z") (pin "P$2") (pinfunction "SIG_P$2") (pintype "bidirectional"))
      (node (ref "U$15") (pin "CMTMOD") (pinfunction "CMTMOD_CMTMOD") (pintype "bidirectional"))
    )
    (net (code "45") (name "Net-(D1-PadC)") (class "Default")
      (node (ref "D1") (pin "C") (pinfunction "C_C") (pintype "passive"))
      (node (ref "R9") (pin "2") (pinfunction "2_2") (pintype "passive"))
    )
    (net (code "46") (name "Net-(D3-PadC)") (class "Default")
      (node (ref "D3") (pin "C") (pinfunction "C_C") (pintype "passive"))
      (node (ref "R10") (pin "2") (pinfunction "2_2") (pintype "passive"))
    )
    (net (code "47") (name "Net-(D4-PadC)") (class "Default")
      (node (ref "D4") (pin "C") (pinfunction "C_C") (pintype "passive"))
      (node (ref "R11") (pin "2") (pinfunction "2_2") (pintype "passive"))
    )
    (net (code "48") (name "Net-(DAA_X-SIG)") (class "Default")
      (node (ref "DAA_X") (pin "P$2") (pinfunction "SIG_P$2") (pintype "bidirectional"))
      (node (ref "U$7") (pin "DAA") (pinfunction "DAA_DAA") (pintype "bidirectional"))
    )
    (net (code "49") (name "Net-(DAA_Y-SIG)") (class "Default")
      (node (ref "DAA_Y") (pin "P$2") (pinfunction "SIG_P$2") (pintype "bidirectional"))
      (node (ref "U$12") (pin "DAA") (pinfunction "DAA_DAA") (pintype "bidirectional"))
    )
    (net (code "50") (name "Net-(DAA_Z-SIG)") (class "Default")
      (node (ref "DAA_Z") (pin "P$2") (pinfunction "SIG_P$2") (pintype "bidirectional"))
      (node (ref "U$15") (pin "DAA") (pinfunction "DAA_DAA") (pintype "bidirectional"))
    )
    (net (code "51") (name "Net-(MOTOR_X-PadP$1)") (class "Default")
      (node (ref "MOTOR_X") (pin "P$1") (pinfunction "P$1_P$1") (pintype "bidirectional"))
      (node (ref "U$7") (pin "W") (pinfunction "W_W") (pintype "bidirectional"))
    )
    (net (code "52") (name "Net-(MOTOR_X-PadP$2)") (class "Default")
      (node (ref "MOTOR_X") (pin "P$2") (pinfunction "P$2_P$2") (pintype "bidirectional"))
      (node (ref "U$7") (pin "V") (pinfunction "V_V") (pintype "bidirectional"))
    )
    (net (code "53") (name "Net-(MOTOR_X-PadP$3)") (class "Default")
      (node (ref "MOTOR_X") (pin "P$3") (pinfunction "P$3_P$3") (pintype "bidirectional"))
      (node (ref "U$7") (pin "U") (pinfunction "U_U") (pintype "bidirectional"))
    )
    (net (code "54") (name "Net-(MOTOR_Y-PadP$1)") (class "Default")
      (node (ref "MOTOR_Y") (pin "P$1") (pinfunction "P$1_P$1") (pintype "bidirectional"))
      (node (ref "U$12") (pin "W") (pinfunction "W_W") (pintype "bidirectional"))
    )
    (net (code "55") (name "Net-(MOTOR_Y-PadP$2)") (class "Default")
      (node (ref "MOTOR_Y") (pin "P$2") (pinfunction "P$2_P$2") (pintype "bidirectional"))
      (node (ref "U$12") (pin "V") (pinfunction "V_V") (pintype "bidirectional"))
    )
    (net (code "56") (name "Net-(MOTOR_Y-PadP$3)") (class "Default")
      (node (ref "MOTOR_Y") (pin "P$3") (pinfunction "P$3_P$3") (pintype "bidirectional"))
      (node (ref "U$12") (pin "U") (pinfunction "U_U") (pintype "bidirectional"))
    )
    (net (code "57") (name "Net-(MOTOR_Z-PadP$1)") (class "Default")
      (node (ref "MOTOR_Z") (pin "P$1") (pinfunction "P$1_P$1") (pintype "bidirectional"))
      (node (ref "U$15") (pin "W") (pinfunction "W_W") (pintype "bidirectional"))
    )
    (net (code "58") (name "Net-(MOTOR_Z-PadP$2)") (class "Default")
      (node (ref "MOTOR_Z") (pin "P$2") (pinfunction "P$2_P$2") (pintype "bidirectional"))
      (node (ref "U$15") (pin "V") (pinfunction "V_V") (pintype "bidirectional"))
    )
    (net (code "59") (name "Net-(MOTOR_Z-PadP$3)") (class "Default")
      (node (ref "MOTOR_Z") (pin "P$3") (pinfunction "P$3_P$3") (pintype "bidirectional"))
      (node (ref "U$15") (pin "U") (pinfunction "U_U") (pintype "bidirectional"))
    )
    (net (code "60") (name "Net-(MSP_X_DEBUG-P2.0_TXD)") (class "Default")
      (node (ref "MSP_X_DEBUG") (pin "3") (pinfunction "P2.0_TXD_3") (pintype "bidirectional"))
      (node (ref "U$3") (pin "P2.0_TXD") (pinfunction "P2.0_TXD_P2.0_TXD") (pintype "bidirectional"))
    )
    (net (code "61") (name "Net-(MSP_X_DEBUG-P2.1_RXD)") (class "Default")
      (node (ref "MSP_X_DEBUG") (pin "4") (pinfunction "P2.1_RXD_4") (pintype "bidirectional"))
      (node (ref "U$3") (pin "P2.1_RXD") (pinfunction "P2.1_RXD_P2.1_RXD") (pintype "bidirectional"))
    )
    (net (code "62") (name "Net-(MSP_X_DEBUG-P3.4_GPIO_DEBUG)") (class "Default")
      (node (ref "MSP_X_DEBUG") (pin "7") (pinfunction "P3.4_GPIO_DEBUG_7") (pintype "bidirectional"))
      (node (ref "U$3") (pin "P3.4_GPIO_DEBUG") (pinfunction "P3.4_GPIO_DEBUG_P3.4_GPIO_DEBUG") (pintype "bidirectional"))
    )
    (net (code "63") (name "Net-(MSP_X_DEBUG-P3.5_GPIO_DEBUG)") (class "Default")
      (node (ref "D1") (pin "A") (pinfunction "A_A") (pintype "passive"))
      (node (ref "MSP_X_DEBUG") (pin "8") (pinfunction "P3.5_GPIO_DEBUG_8") (pintype "bidirectional"))
      (node (ref "U$3") (pin "P3.5_GPIO_DEBUG") (pinfunction "P3.5_GPIO_DEBUG_P3.5_GPIO_DEBUG") (pintype "bidirectional"))
    )
    (net (code "64") (name "Net-(MSP_X_DEBUG-PadSBWTCK)") (class "Default")
      (node (ref "MSP_X_DEBUG") (pin "SBWTCK") (pinfunction "SBWTCK_SBWTCK") (pintype "bidirectional"))
      (node (ref "U$3") (pin "SBWTCK") (pinfunction "SBWTCK_SBWTCK") (pintype "bidirectional"))
    )
    (net (code "65") (name "Net-(MSP_X_DEBUG-SBWTDIO)") (class "Default")
      (node (ref "MSP_X_DEBUG") (pin "2") (pinfunction "SBWTDIO_2") (pintype "bidirectional"))
      (node (ref "U$3") (pin "SBWTDIO") (pinfunction "SBWTDIO_SBWTDIO") (pintype "bidirectional"))
    )
    (net (code "66") (name "Net-(MSP_Y_DEBUG-P2.0_TXD)") (class "Default")
      (node (ref "MSP_Y_DEBUG") (pin "3") (pinfunction "P2.0_TXD_3") (pintype "bidirectional"))
      (node (ref "U$10") (pin "P2.0_TXD") (pinfunction "P2.0_TXD_P2.0_TXD") (pintype "bidirectional"))
    )
    (net (code "67") (name "Net-(MSP_Y_DEBUG-P2.1_RXD)") (class "Default")
      (node (ref "MSP_Y_DEBUG") (pin "4") (pinfunction "P2.1_RXD_4") (pintype "bidirectional"))
      (node (ref "U$10") (pin "P2.1_RXD") (pinfunction "P2.1_RXD_P2.1_RXD") (pintype "bidirectional"))
    )
    (net (code "68") (name "Net-(MSP_Y_DEBUG-P3.4_GPIO_DEBUG)") (class "Default")
      (node (ref "MSP_Y_DEBUG") (pin "7") (pinfunction "P3.4_GPIO_DEBUG_7") (pintype "bidirectional"))
      (node (ref "U$10") (pin "P3.4_GPIO_DEBUG") (pinfunction "P3.4_GPIO_DEBUG_P3.4_GPIO_DEBUG") (pintype "bidirectional"))
    )
    (net (code "69") (name "Net-(MSP_Y_DEBUG-P3.5_GPIO_DEBUG)") (class "Default")
      (node (ref "D3") (pin "A") (pinfunction "A_A") (pintype "passive"))
      (node (ref "MSP_Y_DEBUG") (pin "8") (pinfunction "P3.5_GPIO_DEBUG_8") (pintype "bidirectional"))
      (node (ref "U$10") (pin "P3.5_GPIO_DEBUG") (pinfunction "P3.5_GPIO_DEBUG_P3.5_GPIO_DEBUG") (pintype "bidirectional"))
    )
    (net (code "70") (name "Net-(MSP_Y_DEBUG-PadSBWTCK)") (class "Default")
      (node (ref "MSP_Y_DEBUG") (pin "SBWTCK") (pinfunction "SBWTCK_SBWTCK") (pintype "bidirectional"))
      (node (ref "U$10") (pin "SBWTCK") (pinfunction "SBWTCK_SBWTCK") (pintype "bidirectional"))
    )
    (net (code "71") (name "Net-(MSP_Y_DEBUG-SBWTDIO)") (class "Default")
      (node (ref "MSP_Y_DEBUG") (pin "2") (pinfunction "SBWTDIO_2") (pintype "bidirectional"))
      (node (ref "U$10") (pin "SBWTDIO") (pinfunction "SBWTDIO_SBWTDIO") (pintype "bidirectional"))
    )
    (net (code "72") (name "Net-(MSP_Z_DEBUG-P2.0_TXD)") (class "Default")
      (node (ref "MSP_Z_DEBUG") (pin "3") (pinfunction "P2.0_TXD_3") (pintype "bidirectional"))
      (node (ref "U$13") (pin "P2.0_TXD") (pinfunction "P2.0_TXD_P2.0_TXD") (pintype "bidirectional"))
    )
    (net (code "73") (name "Net-(MSP_Z_DEBUG-P2.1_RXD)") (class "Default")
      (node (ref "MSP_Z_DEBUG") (pin "4") (pinfunction "P2.1_RXD_4") (pintype "bidirectional"))
      (node (ref "U$13") (pin "P2.1_RXD") (pinfunction "P2.1_RXD_P2.1_RXD") (pintype "bidirectional"))
    )
    (net (code "74") (name "Net-(MSP_Z_DEBUG-P3.4_GPIO_DEBUG)") (class "Default")
      (node (ref "MSP_Z_DEBUG") (pin "7") (pinfunction "P3.4_GPIO_DEBUG_7") (pintype "bidirectional"))
      (node (ref "U$13") (pin "P3.4_GPIO_DEBUG") (pinfunction "P3.4_GPIO_DEBUG_P3.4_GPIO_DEBUG") (pintype "bidirectional"))
    )
    (net (code "75") (name "Net-(MSP_Z_DEBUG-P3.5_GPIO_DEBUG)") (class "Default")
      (node (ref "D4") (pin "A") (pinfunction "A_A") (pintype "passive"))
      (node (ref "MSP_Z_DEBUG") (pin "8") (pinfunction "P3.5_GPIO_DEBUG_8") (pintype "bidirectional"))
      (node (ref "U$13") (pin "P3.5_GPIO_DEBUG") (pinfunction "P3.5_GPIO_DEBUG_P3.5_GPIO_DEBUG") (pintype "bidirectional"))
    )
    (net (code "76") (name "Net-(MSP_Z_DEBUG-PadSBWTCK)") (class "Default")
      (node (ref "MSP_Z_DEBUG") (pin "SBWTCK") (pinfunction "SBWTCK_SBWTCK") (pintype "bidirectional"))
      (node (ref "U$13") (pin "SBWTCK") (pinfunction "SBWTCK_SBWTCK") (pintype "bidirectional"))
    )
    (net (code "77") (name "Net-(MSP_Z_DEBUG-SBWTDIO)") (class "Default")
      (node (ref "MSP_Z_DEBUG") (pin "2") (pinfunction "SBWTDIO_2") (pintype "bidirectional"))
      (node (ref "U$13") (pin "SBWTDIO") (pinfunction "SBWTDIO_SBWTDIO") (pintype "bidirectional"))
    )
    (net (code "78") (name "Net-(R2-Pad2)") (class "Default")
      (node (ref "R2") (pin "2") (pinfunction "2_2") (pintype "passive"))
      (node (ref "R3") (pin "1") (pinfunction "1_1") (pintype "passive"))
      (node (ref "U$7") (pin "U_HN") (pinfunction "U_HN_U_HN") (pintype "bidirectional"))
      (node (ref "U$7") (pin "V_HN") (pinfunction "V_HN_V_HN") (pintype "bidirectional"))
      (node (ref "U$7") (pin "W_HN") (pinfunction "W_HN_W_HN") (pintype "bidirectional"))
    )
    (net (code "79") (name "Net-(R7-Pad2)") (class "Default")
      (node (ref "R7") (pin "2") (pinfunction "2_2") (pintype "passive"))
      (node (ref "U$7") (pin "CS") (pinfunction "CS_CS") (pintype "bidirectional"))
    )
    (net (code "80") (name "Net-(R18-Pad2)") (class "Default")
      (node (ref "R18") (pin "2") (pinfunction "2_2") (pintype "passive"))
      (node (ref "R19") (pin "1") (pinfunction "1_1") (pintype "passive"))
      (node (ref "U$12") (pin "U_HN") (pinfunction "U_HN_U_HN") (pintype "bidirectional"))
      (node (ref "U$12") (pin "V_HN") (pinfunction "V_HN_V_HN") (pintype "bidirectional"))
      (node (ref "U$12") (pin "W_HN") (pinfunction "W_HN_W_HN") (pintype "bidirectional"))
    )
    (net (code "81") (name "Net-(R23-Pad2)") (class "Default")
      (node (ref "R23") (pin "2") (pinfunction "2_2") (pintype "passive"))
      (node (ref "U$12") (pin "CS") (pinfunction "CS_CS") (pintype "bidirectional"))
    )
    (net (code "82") (name "Net-(R26-Pad2)") (class "Default")
      (node (ref "R26") (pin "2") (pinfunction "2_2") (pintype "passive"))
      (node (ref "R27") (pin "1") (pinfunction "1_1") (pintype "passive"))
      (node (ref "U$15") (pin "U_HN") (pinfunction "U_HN_U_HN") (pintype "bidirectional"))
      (node (ref "U$15") (pin "V_HN") (pinfunction "V_HN_V_HN") (pintype "bidirectional"))
      (node (ref "U$15") (pin "W_HN") (pinfunction "W_HN_W_HN") (pintype "bidirectional"))
    )
    (net (code "83") (name "Net-(R31-Pad2)") (class "Default")
      (node (ref "R31") (pin "2") (pinfunction "2_2") (pintype "passive"))
      (node (ref "U$15") (pin "CS") (pinfunction "CS_CS") (pintype "bidirectional"))
    )
    (net (code "84") (name "Net-(U2-BYP)") (class "Default")
      (node (ref "C16") (pin "2") (pinfunction "2_2") (pintype "passive"))
      (node (ref "U2") (pin "P$4") (pinfunction "BYP_P$4") (pintype "bidirectional"))
    )
    (net (code "85") (name "Net-(U3-BYP)") (class "Default")
      (node (ref "C29") (pin "2") (pinfunction "2_2") (pintype "passive"))
      (node (ref "U3") (pin "P$4") (pinfunction "BYP_P$4") (pintype "bidirectional"))
    )
    (net (code "86") (name "PWM_X") (class "Default")
      (node (ref "MOTOR_X_DEBUG") (pin "3") (pinfunction "3_3") (pintype "passive"))
      (node (ref "U$3") (pin "P1.7_GPIO/PWM") (pinfunction "P1.7_GPIO/PWM_P1.7_GPIO/PWM") (pintype "bidirectional"))
      (node (ref "U$7") (pin "PWM") (pinfunction "PWM_PWM") (pintype "bidirectional"))
    )
    (net (code "87") (name "PWM_Y") (class "Default")
      (node (ref "MOTOR_Y_DEBUG") (pin "3") (pinfunction "3_3") (pintype "passive"))
      (node (ref "U$10") (pin "P1.7_GPIO/PWM") (pinfunction "P1.7_GPIO/PWM_P1.7_GPIO/PWM") (pintype "bidirectional"))
      (node (ref "U$12") (pin "PWM") (pinfunction "PWM_PWM") (pintype "bidirectional"))
    )
    (net (code "88") (name "PWM_Z") (class "Default")
      (node (ref "MOTOR_Z_DEBUG") (pin "3") (pinfunction "3_3") (pintype "passive"))
      (node (ref "U$13") (pin "P1.7_GPIO/PWM") (pinfunction "P1.7_GPIO/PWM_P1.7_GPIO/PWM") (pintype "bidirectional"))
      (node (ref "U$15") (pin "PWM") (pinfunction "PWM_PWM") (pintype "bidirectional"))
    )
    (net (code "89") (name "RD_X") (class "Default")
      (node (ref "R1") (pin "1") (pinfunction "1_1") (pintype "passive"))
      (node (ref "U$3") (pin "P4.0_GPIO") (pinfunction "P4.0_GPIO_P4.0_GPIO") (pintype "bidirectional"))
      (node (ref "U$7") (pin "RD") (pinfunction "RD_RD") (pintype "bidirectional"))
    )
    (net (code "90") (name "RD_Y") (class "Default")
      (node (ref "R17") (pin "1") (pinfunction "1_1") (pintype "passive"))
      (node (ref "U$10") (pin "P4.0_GPIO") (pinfunction "P4.0_GPIO_P4.0_GPIO") (pintype "bidirectional"))
      (node (ref "U$12") (pin "RD") (pinfunction "RD_RD") (pintype "bidirectional"))
    )
    (net (code "91") (name "RD_Z") (class "Default")
      (node (ref "R25") (pin "1") (pinfunction "1_1") (pintype "passive"))
      (node (ref "U$13") (pin "P4.0_GPIO") (pinfunction "P4.0_GPIO_P4.0_GPIO") (pintype "bidirectional"))
      (node (ref "U$15") (pin "RD") (pinfunction "RD_RD") (pintype "bidirectional"))
    )
    (net (code "92") (name "SYNC1") (class "Default")
      (node (ref "PC104") (pin "P$45") (pinfunction "SYNC1_P$45") (pintype "bidirectional"))
      (node (ref "U$10") (pin "P7.2_SYNC1") (pinfunction "P7.2_SYNC1_P7.2_SYNC1") (pintype "bidirectional"))
      (node (ref "U$13") (pin "P7.2_SYNC1") (pinfunction "P7.2_SYNC1_P7.2_SYNC1") (pintype "bidirectional"))
      (node (ref "U$3") (pin "P7.2_SYNC1") (pinfunction "P7.2_SYNC1_P7.2_SYNC1") (pintype "bidirectional"))
    )
    (net (code "93") (name "SYNC2") (class "Default")
      (node (ref "PC104") (pin "P$49") (pinfunction "SYNC2_P$49") (pintype "bidirectional"))
      (node (ref "U$10") (pin "PJ.3_SYNC2") (pinfunction "PJ.3_SYNC2_PJ.3_SYNC2") (pintype "bidirectional"))
      (node (ref "U$13") (pin "PJ.3_SYNC2") (pinfunction "PJ.3_SYNC2_PJ.3_SYNC2") (pintype "bidirectional"))
      (node (ref "U$3") (pin "PJ.3_SYNC2") (pinfunction "PJ.3_SYNC2_PJ.3_SYNC2") (pintype "bidirectional"))
    )
    (net (code "94") (name "VBAT") (class "Default")
      (node (ref "C15") (pin "2") (pinfunction "2_2") (pintype "passive"))
      (node (ref "C17") (pin "2") (pinfunction "2_2") (pintype "passive"))
      (node (ref "C22") (pin "2") (pinfunction "2_2") (pintype "passive"))
      (node (ref "C30") (pin "2") (pinfunction "2_2") (pintype "passive"))
      (node (ref "C5") (pin "2") (pinfunction "2_2") (pintype "passive"))
      (node (ref "C8") (pin "1") (pinfunction "1_1") (pintype "passive"))
      (node (ref "PC104") (pin "P$69") (pinfunction "WHEEL_VBAT_P$69") (pintype "bidirectional"))
      (node (ref "PC104") (pin "P$70") (pinfunction "WHEEL_VBAT_P$70") (pintype "bidirectional"))
      (node (ref "U$12") (pin "VM") (pinfunction "VM_VM") (pintype "bidirectional"))
      (node (ref "U$15") (pin "VM") (pinfunction "VM_VM") (pintype "bidirectional"))
      (node (ref "U$7") (pin "VM") (pinfunction "VM_VM") (pintype "bidirectional"))
      (node (ref "U2") (pin "P$1") (pinfunction "IN_P$1") (pintype "bidirectional"))
      (node (ref "U2") (pin "P$3") (pinfunction "EN_P$3") (pintype "bidirectional"))
      (node (ref "U3") (pin "P$1") (pinfunction "IN_P$1") (pintype "bidirectional"))
      (node (ref "U3") (pin "P$3") (pinfunction "EN_P$3") (pintype "bidirectional"))
    )
    (net (code "95") (name "VINT_X") (class "Default")
      (node (ref "C4") (pin "2") (pinfunction "2_2") (pintype "passive"))
      (node (ref "CMTMOD_X") (pin "P$3") (pinfunction "VCC_P$3") (pintype "bidirectional"))
      (node (ref "DAA_X") (pin "P$3") (pinfunction "VCC_P$3") (pintype "bidirectional"))
      (node (ref "MOTOR_X") (pin "P$5") (pinfunction "P$5_P$5") (pintype "bidirectional"))
      (node (ref "R1") (pin "2") (pinfunction "2_2") (pintype "passive"))
      (node (ref "R3") (pin "2") (pinfunction "2_2") (pintype "passive"))
      (node (ref "R4") (pin "1") (pinfunction "1_1") (pintype "passive"))
      (node (ref "R5") (pin "1") (pinfunction "1_1") (pintype "passive"))
      (node (ref "R6") (pin "1") (pinfunction "1_1") (pintype "passive"))
      (node (ref "R8") (pin "1") (pinfunction "1_1") (pintype "passive"))
      (node (ref "U$7") (pin "VINT") (pinfunction "VINT_VINT") (pintype "bidirectional"))
    )
    (net (code "96") (name "VINT_Y") (class "Default")
      (node (ref "C14") (pin "2") (pinfunction "2_2") (pintype "passive"))
      (node (ref "CMTMOD_Y") (pin "P$3") (pinfunction "VCC_P$3") (pintype "bidirectional"))
      (node (ref "DAA_Y") (pin "P$3") (pinfunction "VCC_P$3") (pintype "bidirectional"))
      (node (ref "MOTOR_Y") (pin "P$5") (pinfunction "P$5_P$5") (pintype "bidirectional"))
      (node (ref "R17") (pin "2") (pinfunction "2_2") (pintype "passive"))
      (node (ref "R19") (pin "2") (pinfunction "2_2") (pintype "passive"))
      (node (ref "R20") (pin "1") (pinfunction "1_1") (pintype "passive"))
      (node (ref "R21") (pin "1") (pinfunction "1_1") (pintype "passive"))
      (node (ref "R22") (pin "1") (pinfunction "1_1") (pintype "passive"))
      (node (ref "R24") (pin "1") (pinfunction "1_1") (pintype "passive"))
      (node (ref "U$12") (pin "VINT") (pinfunction "VINT_VINT") (pintype "bidirectional"))
    )
    (net (code "97") (name "VINT_Z") (class "Default")
      (node (ref "C21") (pin "2") (pinfunction "2_2") (pintype "passive"))
      (node (ref "CMTMOD_Z") (pin "P$3") (pinfunction "VCC_P$3") (pintype "bidirectional"))
      (node (ref "DAA_Z") (pin "P$3") (pinfunction "VCC_P$3") (pintype "bidirectional"))
      (node (ref "MOTOR_Z") (pin "P$5") (pinfunction "P$5_P$5") (pintype "bidirectional"))
      (node (ref "R25") (pin "2") (pinfunction "2_2") (pintype "passive"))
      (node (ref "R27") (pin "2") (pinfunction "2_2") (pintype "passive"))
      (node (ref "R28") (pin "1") (pinfunction "1_1") (pintype "passive"))
      (node (ref "R29") (pin "1") (pinfunction "1_1") (pintype "passive"))
      (node (ref "R30") (pin "1") (pinfunction "1_1") (pintype "passive"))
      (node (ref "R32") (pin "1") (pinfunction "1_1") (pintype "passive"))
      (node (ref "U$15") (pin "VINT") (pinfunction "VINT_VINT") (pintype "bidirectional"))
    )
    (net (code "98") (name "unconnected-(PC104-BATT_VBAT$33-PadP$33)") (class "Default")
      (node (ref "PC104") (pin "P$33") (pinfunction "BATT_VBAT$33_P$33") (pintype "bidirectional"))
    )
    (net (code "99") (name "unconnected-(PC104-BATT_VBATT$34-PadP$34)") (class "Default")
      (node (ref "PC104") (pin "P$34") (pinfunction "BATT_VBATT$34_P$34") (pintype "bidirectional"))
    )
    (net (code "100") (name "unconnected-(PC104-BDOT_GND-PadP$87)") (class "Default")
      (node (ref "PC104") (pin "P$87") (pinfunction "BDOT_GND_P$87") (pintype "bidirectional"))
    )
    (net (code "101") (name "unconnected-(PC104-BDOT_GND-PadP$88)") (class "Default")
      (node (ref "PC104") (pin "P$88") (pinfunction "BDOT_GND_P$88") (pintype "bidirectional"))
    )
    (net (code "102") (name "unconnected-(PC104-BDOT_VBAT-PadP$85)") (class "Default")
      (node (ref "PC104") (pin "P$85") (pinfunction "BDOT_VBAT_P$85") (pintype "bidirectional"))
    )
    (net (code "103") (name "unconnected-(PC104-BDOT_VBAT-PadP$86)") (class "Default")
      (node (ref "PC104") (pin "P$86") (pinfunction "BDOT_VBAT_P$86") (pintype "bidirectional"))
    )
    (net (code "104") (name "unconnected-(PC104-COM1_GND-PadP$102)") (class "Default")
      (node (ref "PC104") (pin "P$102") (pinfunction "COM1_GND_P$102") (pintype "bidirectional"))
    )
    (net (code "105") (name "unconnected-(PC104-COM1_GND-PadP$104)") (class "Default")
      (node (ref "PC104") (pin "P$104") (pinfunction "COM1_GND_P$104") (pintype "bidirectional"))
    )
    (net (code "106") (name "unconnected-(PC104-COM1_VBAT-PadP$101)") (class "Default")
      (node (ref "PC104") (pin "P$101") (pinfunction "COM1_VBAT_P$101") (pintype "bidirectional"))
    )
    (net (code "107") (name "unconnected-(PC104-COM1_VBAT-PadP$103)") (class "Default")
      (node (ref "PC104") (pin "P$103") (pinfunction "COM1_VBAT_P$103") (pintype "bidirectional"))
    )
    (net (code "108") (name "unconnected-(PC104-COM2_GND-PadP$98)") (class "Default")
      (node (ref "PC104") (pin "P$98") (pinfunction "COM2_GND_P$98") (pintype "bidirectional"))
    )
    (net (code "109") (name "unconnected-(PC104-COM2_GND-PadP$100)") (class "Default")
      (node (ref "PC104") (pin "P$100") (pinfunction "COM2_GND_P$100") (pintype "bidirectional"))
    )
    (net (code "110") (name "unconnected-(PC104-COM2_VBAT-PadP$97)") (class "Default")
      (node (ref "PC104") (pin "P$97") (pinfunction "COM2_VBAT_P$97") (pintype "bidirectional"))
    )
    (net (code "111") (name "unconnected-(PC104-COM2_VBAT-PadP$99)") (class "Default")
      (node (ref "PC104") (pin "P$99") (pinfunction "COM2_VBAT_P$99") (pintype "bidirectional"))
    )
    (net (code "112") (name "unconnected-(PC104-DISTRI_GND-PadP$17)") (class "Default")
      (node (ref "PC104") (pin "P$17") (pinfunction "DISTRI_GND_P$17") (pintype "bidirectional"))
    )
    (net (code "113") (name "unconnected-(PC104-DISTRI_GND-PadP$19)") (class "Default")
      (node (ref "PC104") (pin "P$19") (pinfunction "DISTRI_GND_P$19") (pintype "bidirectional"))
    )
    (net (code "114") (name "unconnected-(PC104-DISTRI_GND-PadP$22)") (class "Default")
      (node (ref "PC104") (pin "P$22") (pinfunction "DISTRI_GND_P$22") (pintype "bidirectional"))
    )
    (net (code "115") (name "unconnected-(PC104-DISTRI_GND-PadP$24)") (class "Default")
      (node (ref "PC104") (pin "P$24") (pinfunction "DISTRI_GND_P$24") (pintype "bidirectional"))
    )
    (net (code "116") (name "unconnected-(PC104-DISTRI_GND-PadP$25)") (class "Default")
      (node (ref "PC104") (pin "P$25") (pinfunction "DISTRI_GND_P$25") (pintype "bidirectional"))
    )
    (net (code "117") (name "unconnected-(PC104-DISTRI_GND-PadP$27)") (class "Default")
      (node (ref "PC104") (pin "P$27") (pinfunction "DISTRI_GND_P$27") (pintype "bidirectional"))
    )
    (net (code "118") (name "unconnected-(PC104-DISTRI_GND-PadP$30)") (class "Default")
      (node (ref "PC104") (pin "P$30") (pinfunction "DISTRI_GND_P$30") (pintype "bidirectional"))
    )
    (net (code "119") (name "unconnected-(PC104-DISTRI_GND-PadP$32)") (class "Default")
      (node (ref "PC104") (pin "P$32") (pinfunction "DISTRI_GND_P$32") (pintype "bidirectional"))
    )
    (net (code "120") (name "unconnected-(PC104-DISTRI_VBAT-PadP$18)") (class "Default")
      (node (ref "PC104") (pin "P$18") (pinfunction "DISTRI_VBAT_P$18") (pintype "bidirectional"))
    )
    (net (code "121") (name "unconnected-(PC104-DISTRI_VBAT-PadP$20)") (class "Default")
      (node (ref "PC104") (pin "P$20") (pinfunction "DISTRI_VBAT_P$20") (pintype "bidirectional"))
    )
    (net (code "122") (name "unconnected-(PC104-DISTRI_VBAT-PadP$21)") (class "Default")
      (node (ref "PC104") (pin "P$21") (pinfunction "DISTRI_VBAT_P$21") (pintype "bidirectional"))
    )
    (net (code "123") (name "unconnected-(PC104-DISTRI_VBAT-PadP$23)") (class "Default")
      (node (ref "PC104") (pin "P$23") (pinfunction "DISTRI_VBAT_P$23") (pintype "bidirectional"))
    )
    (net (code "124") (name "unconnected-(PC104-DISTRI_VBAT-PadP$26)") (class "Default")
      (node (ref "PC104") (pin "P$26") (pinfunction "DISTRI_VBAT_P$26") (pintype "bidirectional"))
    )
    (net (code "125") (name "unconnected-(PC104-DISTRI_VBAT-PadP$28)") (class "Default")
      (node (ref "PC104") (pin "P$28") (pinfunction "DISTRI_VBAT_P$28") (pintype "bidirectional"))
    )
    (net (code "126") (name "unconnected-(PC104-DISTRI_VBAT-PadP$29)") (class "Default")
      (node (ref "PC104") (pin "P$29") (pinfunction "DISTRI_VBAT_P$29") (pintype "bidirectional"))
    )
    (net (code "127") (name "unconnected-(PC104-DISTRI_VBAT-PadP$31)") (class "Default")
      (node (ref "PC104") (pin "P$31") (pinfunction "DISTRI_VBAT_P$31") (pintype "bidirectional"))
    )
    (net (code "128") (name "unconnected-(PC104-ESTIMAT_GND-PadP$79)") (class "Default")
      (node (ref "PC104") (pin "P$79") (pinfunction "ESTIMAT_GND_P$79") (pintype "bidirectional"))
    )
    (net (code "129") (name "unconnected-(PC104-ESTIMAT_GND-PadP$80)") (class "Default")
      (node (ref "PC104") (pin "P$80") (pinfunction "ESTIMAT_GND_P$80") (pintype "bidirectional"))
    )
    (net (code "130") (name "unconnected-(PC104-ESTIMAT_VBAT-PadP$77)") (class "Default")
      (node (ref "PC104") (pin "P$77") (pinfunction "ESTIMAT_VBAT_P$77") (pintype "bidirectional"))
    )
    (net (code "131") (name "unconnected-(PC104-ESTIMAT_VBAT-PadP$78)") (class "Default")
      (node (ref "PC104") (pin "P$78") (pinfunction "ESTIMAT_VBAT_P$78") (pintype "bidirectional"))
    )
    (net (code "132") (name "unconnected-(PC104-GEN_VBATT$35-PadP$35)") (class "Default")
      (node (ref "PC104") (pin "P$35") (pinfunction "GEN_VBATT$35_P$35") (pintype "bidirectional"))
    )
    (net (code "133") (name "unconnected-(PC104-GEN_VBATT$36-PadP$36)") (class "Default")
      (node (ref "PC104") (pin "P$36") (pinfunction "GEN_VBATT$36_P$36") (pintype "bidirectional"))
    )
    (net (code "134") (name "unconnected-(PC104-P-PadP$59)") (class "Default")
      (node (ref "PC104") (pin "P$59") (pinfunction "P_P$59") (pintype "bidirectional"))
    )
    (net (code "135") (name "unconnected-(PC104-PPT_GND-PadP$1)") (class "Default")
      (node (ref "PC104") (pin "P$1") (pinfunction "PPT_GND_P$1") (pintype "bidirectional"))
    )
    (net (code "136") (name "unconnected-(PC104-PPT_GND-PadP$3)") (class "Default")
      (node (ref "PC104") (pin "P$3") (pinfunction "PPT_GND_P$3") (pintype "bidirectional"))
    )
    (net (code "137") (name "unconnected-(PC104-PPT_GND-PadP$6)") (class "Default")
      (node (ref "PC104") (pin "P$6") (pinfunction "PPT_GND_P$6") (pintype "bidirectional"))
    )
    (net (code "138") (name "unconnected-(PC104-PPT_GND-PadP$8)") (class "Default")
      (node (ref "PC104") (pin "P$8") (pinfunction "PPT_GND_P$8") (pintype "bidirectional"))
    )
    (net (code "139") (name "unconnected-(PC104-PPT_GND-PadP$9)") (class "Default")
      (node (ref "PC104") (pin "P$9") (pinfunction "PPT_GND_P$9") (pintype "bidirectional"))
    )
    (net (code "140") (name "unconnected-(PC104-PPT_GND-PadP$11)") (class "Default")
      (node (ref "PC104") (pin "P$11") (pinfunction "PPT_GND_P$11") (pintype "bidirectional"))
    )
    (net (code "141") (name "unconnected-(PC104-PPT_GND-PadP$14)") (class "Default")
      (node (ref "PC104") (pin "P$14") (pinfunction "PPT_GND_P$14") (pintype "bidirectional"))
    )
    (net (code "142") (name "unconnected-(PC104-PPT_GND-PadP$16)") (class "Default")
      (node (ref "PC104") (pin "P$16") (pinfunction "PPT_GND_P$16") (pintype "bidirectional"))
    )
    (net (code "143") (name "unconnected-(PC104-PPT_VBAT-PadP$2)") (class "Default")
      (node (ref "PC104") (pin "P$2") (pinfunction "PPT_VBAT_P$2") (pintype "bidirectional"))
    )
    (net (code "144") (name "unconnected-(PC104-PPT_VBAT-PadP$4)") (class "Default")
      (node (ref "PC104") (pin "P$4") (pinfunction "PPT_VBAT_P$4") (pintype "bidirectional"))
    )
    (net (code "145") (name "unconnected-(PC104-PPT_VBAT-PadP$5)") (class "Default")
      (node (ref "PC104") (pin "P$5") (pinfunction "PPT_VBAT_P$5") (pintype "bidirectional"))
    )
    (net (code "146") (name "unconnected-(PC104-PPT_VBAT-PadP$7)") (class "Default")
      (node (ref "PC104") (pin "P$7") (pinfunction "PPT_VBAT_P$7") (pintype "bidirectional"))
    )
    (net (code "147") (name "unconnected-(PC104-PPT_VBAT-PadP$10)") (class "Default")
      (node (ref "PC104") (pin "P$10") (pinfunction "PPT_VBAT_P$10") (pintype "bidirectional"))
    )
    (net (code "148") (name "unconnected-(PC104-PPT_VBAT-PadP$12)") (class "Default")
      (node (ref "PC104") (pin "P$12") (pinfunction "PPT_VBAT_P$12") (pintype "bidirectional"))
    )
    (net (code "149") (name "unconnected-(PC104-PPT_VBAT-PadP$13)") (class "Default")
      (node (ref "PC104") (pin "P$13") (pinfunction "PPT_VBAT_P$13") (pintype "bidirectional"))
    )
    (net (code "150") (name "unconnected-(PC104-PPT_VBAT-PadP$15)") (class "Default")
      (node (ref "PC104") (pin "P$15") (pinfunction "PPT_VBAT_P$15") (pintype "bidirectional"))
    )
    (net (code "151") (name "unconnected-(PC104-PadP$37)") (class "Default")
      (node (ref "PC104") (pin "P$37") (pinfunction "P$37_P$37") (pintype "bidirectional"))
    )
    (net (code "152") (name "unconnected-(PC104-PadP$38)") (class "Default")
      (node (ref "PC104") (pin "P$38") (pinfunction "P$38_P$38") (pintype "bidirectional"))
    )
    (net (code "153") (name "unconnected-(PC104-PadP$39)") (class "Default")
      (node (ref "PC104") (pin "P$39") (pinfunction "P$39_P$39") (pintype "bidirectional"))
    )
    (net (code "154") (name "unconnected-(PC104-PadP$40)") (class "Default")
      (node (ref "PC104") (pin "P$40") (pinfunction "P$40_P$40") (pintype "bidirectional"))
    )
    (net (code "155") (name "unconnected-(PC104-PadP$41)") (class "Default")
      (node (ref "PC104") (pin "P$41") (pinfunction "P$41_P$41") (pintype "bidirectional"))
    )
    (net (code "156") (name "unconnected-(PC104-PadP$42)") (class "Default")
      (node (ref "PC104") (pin "P$42") (pinfunction "P$42_P$42") (pintype "bidirectional"))
    )
    (net (code "157") (name "unconnected-(PC104-PadP$43)") (class "Default")
      (node (ref "PC104") (pin "P$43") (pinfunction "P$43_P$43") (pintype "bidirectional"))
    )
    (net (code "158") (name "unconnected-(PC104-PadP$44)") (class "Default")
      (node (ref "PC104") (pin "P$44") (pinfunction "P$44_P$44") (pintype "bidirectional"))
    )
    (net (code "159") (name "unconnected-(PC104-PadP$46)") (class "Default")
      (node (ref "PC104") (pin "P$46") (pinfunction "P$46_P$46") (pintype "bidirectional"))
    )
    (net (code "160") (name "unconnected-(PC104-PadP$47)") (class "Default")
      (node (ref "PC104") (pin "P$47") (pinfunction "P$47_P$47") (pintype "bidirectional"))
    )
    (net (code "161") (name "unconnected-(PC104-PadP$48)") (class "Default")
      (node (ref "PC104") (pin "P$48") (pinfunction "P$48_P$48") (pintype "bidirectional"))
    )
    (net (code "162") (name "unconnected-(PC104-PadP$50)") (class "Default")
      (node (ref "PC104") (pin "P$50") (pinfunction "P$50_P$50") (pintype "bidirectional"))
    )
    (net (code "163") (name "unconnected-(PC104-PadP$54)") (class "Default")
      (node (ref "PC104") (pin "P$54") (pinfunction "P$54_P$54") (pintype "bidirectional"))
    )
    (net (code "164") (name "unconnected-(PC104-PadP$58)") (class "Default")
      (node (ref "PC104") (pin "P$58") (pinfunction "P$58_P$58") (pintype "bidirectional"))
    )
    (net (code "165") (name "unconnected-(PC104-PadP$60)") (class "Default")
      (node (ref "PC104") (pin "P$60") (pinfunction "P$60_P$60") (pintype "bidirectional"))
    )
    (net (code "166") (name "unconnected-(PC104-PadP$61)") (class "Default")
      (node (ref "PC104") (pin "P$61") (pinfunction "P$61_P$61") (pintype "bidirectional"))
    )
    (net (code "167") (name "unconnected-(PC104-PadP$62)") (class "Default")
      (node (ref "PC104") (pin "P$62") (pinfunction "P$62_P$62") (pintype "bidirectional"))
    )
    (net (code "168") (name "unconnected-(PC104-PadP$63)") (class "Default")
      (node (ref "PC104") (pin "P$63") (pinfunction "P$63_P$63") (pintype "bidirectional"))
    )
    (net (code "169") (name "unconnected-(PC104-PadP$64)") (class "Default")
      (node (ref "PC104") (pin "P$64") (pinfunction "P$64_P$64") (pintype "bidirectional"))
    )
    (net (code "170") (name "unconnected-(PC104-PadP$65)") (class "Default")
      (node (ref "PC104") (pin "P$65") (pinfunction "P$65_P$65") (pintype "bidirectional"))
    )
    (net (code "171") (name "unconnected-(PC104-PadP$66)") (class "Default")
      (node (ref "PC104") (pin "P$66") (pinfunction "P$66_P$66") (pintype "bidirectional"))
    )
    (net (code "172") (name "unconnected-(PC104-PadP$67)") (class "Default")
      (node (ref "PC104") (pin "P$67") (pinfunction "P$67_P$67") (pintype "bidirectional"))
    )
    (net (code "173") (name "unconnected-(PC104-PadP$68)") (class "Default")
      (node (ref "PC104") (pin "P$68") (pinfunction "P$68_P$68") (pintype "bidirectional"))
    )
    (net (code "174") (name "unconnected-(PC104-PadP$73)") (class "Default")
      (node (ref "PC104") (pin "P$73") (pinfunction "P$73_P$73") (pintype "bidirectional"))
    )
    (net (code "175") (name "unconnected-(PC104-PadP$74)") (class "Default")
      (node (ref "PC104") (pin "P$74") (pinfunction "P$74_P$74") (pintype "bidirectional"))
    )
    (net (code "176") (name "unconnected-(PC104-PadP$75)") (class "Default")
      (node (ref "PC104") (pin "P$75") (pinfunction "P$75_P$75") (pintype "bidirectional"))
    )
    (net (code "177") (name "unconnected-(PC104-PadP$76)") (class "Default")
      (node (ref "PC104") (pin "P$76") (pinfunction "P$76_P$76") (pintype "bidirectional"))
    )
    (net (code "178") (name "unconnected-(PC104-PadP$81)") (class "Default")
      (node (ref "PC104") (pin "P$81") (pinfunction "P$81_P$81") (pintype "bidirectional"))
    )
    (net (code "179") (name "unconnected-(PC104-PadP$82)") (class "Default")
      (node (ref "PC104") (pin "P$82") (pinfunction "P$82_P$82") (pintype "bidirectional"))
    )
    (net (code "180") (name "unconnected-(PC104-PadP$83)") (class "Default")
      (node (ref "PC104") (pin "P$83") (pinfunction "P$83_P$83") (pintype "bidirectional"))
    )
    (net (code "181") (name "unconnected-(PC104-PadP$84)") (class "Default")
      (node (ref "PC104") (pin "P$84") (pinfunction "P$84_P$84") (pintype "bidirectional"))
    )
    (net (code "182") (name "unconnected-(PC104-PadP$89)") (class "Default")
      (node (ref "PC104") (pin "P$89") (pinfunction "P$89_P$89") (pintype "bidirectional"))
    )
    (net (code "183") (name "unconnected-(PC104-PadP$90)") (class "Default")
      (node (ref "PC104") (pin "P$90") (pinfunction "P$90_P$90") (pintype "bidirectional"))
    )
    (net (code "184") (name "unconnected-(PC104-PadP$91)") (class "Default")
      (node (ref "PC104") (pin "P$91") (pinfunction "P$91_P$91") (pintype "bidirectional"))
    )
    (net (code "185") (name "unconnected-(PC104-PadP$92)") (class "Default")
      (node (ref "PC104") (pin "P$92") (pinfunction "P$92_P$92") (pintype "bidirectional"))
    )
    (net (code "186") (name "unconnected-(PC104-PadP$95)") (class "Default")
      (node (ref "PC104") (pin "P$95") (pinfunction "P$95_P$95") (pintype "bidirectional"))
    )
    (net (code "187") (name "unconnected-(PC104-PadP$96)") (class "Default")
      (node (ref "PC104") (pin "P$96") (pinfunction "P$96_P$96") (pintype "bidirectional"))
    )
    (net (code "188") (name "unconnected-(PC104-RAHS_GND-PadP$94)") (class "Default")
      (node (ref "PC104") (pin "P$94") (pinfunction "RAHS_GND_P$94") (pintype "bidirectional"))
    )
    (net (code "189") (name "unconnected-(PC104-RAHS_VBAT-PadP$93)") (class "Default")
      (node (ref "PC104") (pin "P$93") (pinfunction "RAHS_VBAT_P$93") (pintype "bidirectional"))
    )
    (net (code "190") (name "unconnected-(PC104-TOPDEPLOY+-PadP$51)") (class "Default")
      (node (ref "PC104") (pin "P$51") (pinfunction "TOPDEPLOY+_P$51") (pintype "bidirectional"))
    )
    (net (code "191") (name "unconnected-(PC104-TOPDEPLOY+-PadP$55)") (class "Default")
      (node (ref "PC104") (pin "P$55") (pinfunction "TOPDEPLOY+_P$55") (pintype "bidirectional"))
    )
    (net (code "192") (name "unconnected-(PC104-TOPDEPLOY-$52-PadP$52)") (class "Default")
      (node (ref "PC104") (pin "P$52") (pinfunction "TOPDEPLOY-$52_P$52") (pintype "bidirectional"))
    )
    (net (code "193") (name "unconnected-(PC104-TOPDEPLOY-$56-PadP$56)") (class "Default")
      (node (ref "PC104") (pin "P$56") (pinfunction "TOPDEPLOY-$56_P$56") (pintype "bidirectional"))
    )
    (net (code "194") (name "unconnected-(U$3-P2.3_SPI-CS2-PadP2.4_SPI-CS2)") (class "Default")
      (node (ref "U$3") (pin "P2.4_SPI-CS2") (pinfunction "P2.3_SPI-CS2_P2.4_SPI-CS2") (pintype "bidirectional"))
    )
    (net (code "195") (name "unconnected-(U$3-PadP1.0_A0)") (class "Default")
      (node (ref "U$3") (pin "P1.0_A0") (pinfunction "P1.0_A0_P1.0_A0") (pintype "bidirectional"))
    )
    (net (code "196") (name "unconnected-(U$3-PadP1.1_A1)") (class "Default")
      (node (ref "U$3") (pin "P1.1_A1") (pinfunction "P1.1_A1_P1.1_A1") (pintype "bidirectional"))
    )
    (net (code "197") (name "unconnected-(U$3-PadP1.2_A2)") (class "Default")
      (node (ref "U$3") (pin "P1.2_A2") (pinfunction "P1.2_A2_P1.2_A2") (pintype "bidirectional"))
    )
    (net (code "198") (name "unconnected-(U$3-PadP1.3_A3)") (class "Default")
      (node (ref "U$3") (pin "P1.3_A3") (pinfunction "P1.3_A3_P1.3_A3") (pintype "bidirectional"))
    )
    (net (code "199") (name "unconnected-(U$3-PadP1.4_A4)") (class "Default")
      (node (ref "U$3") (pin "P1.4_A4") (pinfunction "P1.4_A4_P1.4_A4") (pintype "bidirectional"))
    )
    (net (code "200") (name "unconnected-(U$3-PadP1.5_A5)") (class "Default")
      (node (ref "U$3") (pin "P1.5_A5") (pinfunction "P1.5_A5_P1.5_A5") (pintype "bidirectional"))
    )
    (net (code "201") (name "unconnected-(U$3-PadP2.2_GPIO{slash}PWM)") (class "Default")
      (node (ref "U$3") (pin "P2.2_GPIO/PWM") (pinfunction "P2.2_GPIO/PWM_P2.2_GPIO/PWM") (pintype "bidirectional"))
    )
    (net (code "202") (name "unconnected-(U$3-PadP2.7_SPI-CS3)") (class "Default")
      (node (ref "U$3") (pin "P2.7_SPI-CS3") (pinfunction "P2.7_SPI-CS3_P2.7_SPI-CS3") (pintype "bidirectional"))
    )
    (net (code "203") (name "unconnected-(U$3-PadP3.0_A12)") (class "Default")
      (node (ref "U$3") (pin "P3.0_A12") (pinfunction "P3.0_A12_P3.0_A12") (pintype "bidirectional"))
    )
    (net (code "204") (name "unconnected-(U$3-PadP3.1_A13)") (class "Default")
      (node (ref "U$3") (pin "P3.1_A13") (pinfunction "P3.1_A13_P3.1_A13") (pintype "bidirectional"))
    )
    (net (code "205") (name "unconnected-(U$3-PadP3.2_A14)") (class "Default")
      (node (ref "U$3") (pin "P3.2_A14") (pinfunction "P3.2_A14_P3.2_A14") (pintype "bidirectional"))
    )
    (net (code "206") (name "unconnected-(U$3-PadP3.3_A15)") (class "Default")
      (node (ref "U$3") (pin "P3.3_A15") (pinfunction "P3.3_A15_P3.3_A15") (pintype "bidirectional"))
    )
    (net (code "207") (name "unconnected-(U$3-PadP4.1_GPIO)") (class "Default")
      (node (ref "U$3") (pin "P4.1_GPIO") (pinfunction "P4.1_GPIO_P4.1_GPIO") (pintype "bidirectional"))
    )
    (net (code "208") (name "unconnected-(U$3-PadP4.2_GPIO)") (class "Default")
      (node (ref "U$3") (pin "P4.2_GPIO") (pinfunction "P4.2_GPIO_P4.2_GPIO") (pintype "bidirectional"))
    )
    (net (code "209") (name "unconnected-(U$3-PadP5.0_I2C-SDA-1)") (class "Default")
      (node (ref "U$3") (pin "P5.0_I2C-SDA-1") (pinfunction "P5.0_I2C-SDA-1_P5.0_I2C-SDA-1") (pintype "bidirectional"))
    )
    (net (code "210") (name "unconnected-(U$3-PadP5.1_I2C-SCL-1)") (class "Default")
      (node (ref "U$3") (pin "P5.1_I2C-SCL-1") (pinfunction "P5.1_I2C-SCL-1_P5.1_I2C-SCL-1") (pintype "bidirectional"))
    )
    (net (code "211") (name "unconnected-(U$3-PadP5.4_SPI-MOSI)") (class "Default")
      (node (ref "U$3") (pin "P5.4_SPI-MOSI") (pinfunction "P5.4_SPI-MOSI_P5.4_SPI-MOSI") (pintype "bidirectional"))
    )
    (net (code "212") (name "unconnected-(U$3-PadP5.5_SPI-MISO)") (class "Default")
      (node (ref "U$3") (pin "P5.5_SPI-MISO") (pinfunction "P5.5_SPI-MISO_P5.5_SPI-MISO") (pintype "bidirectional"))
    )
    (net (code "213") (name "unconnected-(U$3-PadP5.6_SPI-CLK)") (class "Default")
      (node (ref "U$3") (pin "P5.6_SPI-CLK") (pinfunction "P5.6_SPI-CLK_P5.6_SPI-CLK") (pintype "bidirectional"))
    )
    (net (code "214") (name "unconnected-(U$3-PadP7.0_I2C-SDA-2)") (class "Default")
      (node (ref "U$3") (pin "P7.0_I2C-SDA-2") (pinfunction "P7.0_I2C-SDA-2_P7.0_I2C-SDA-2") (pintype "bidirectional"))
    )
    (net (code "215") (name "unconnected-(U$3-PadP7.1_I2C-SCL-2)") (class "Default")
      (node (ref "U$3") (pin "P7.1_I2C-SCL-2") (pinfunction "P7.1_I2C-SCL-2_P7.1_I2C-SCL-2") (pintype "bidirectional"))
    )
    (net (code "216") (name "unconnected-(U$10-P2.3_SPI-CS2-PadP2.4_SPI-CS2)") (class "Default")
      (node (ref "U$10") (pin "P2.4_SPI-CS2") (pinfunction "P2.3_SPI-CS2_P2.4_SPI-CS2") (pintype "bidirectional"))
    )
    (net (code "217") (name "unconnected-(U$10-PadP1.0_A0)") (class "Default")
      (node (ref "U$10") (pin "P1.0_A0") (pinfunction "P1.0_A0_P1.0_A0") (pintype "bidirectional"))
    )
    (net (code "218") (name "unconnected-(U$10-PadP1.1_A1)") (class "Default")
      (node (ref "U$10") (pin "P1.1_A1") (pinfunction "P1.1_A1_P1.1_A1") (pintype "bidirectional"))
    )
    (net (code "219") (name "unconnected-(U$10-PadP1.2_A2)") (class "Default")
      (node (ref "U$10") (pin "P1.2_A2") (pinfunction "P1.2_A2_P1.2_A2") (pintype "bidirectional"))
    )
    (net (code "220") (name "unconnected-(U$10-PadP1.3_A3)") (class "Default")
      (node (ref "U$10") (pin "P1.3_A3") (pinfunction "P1.3_A3_P1.3_A3") (pintype "bidirectional"))
    )
    (net (code "221") (name "unconnected-(U$10-PadP1.4_A4)") (class "Default")
      (node (ref "U$10") (pin "P1.4_A4") (pinfunction "P1.4_A4_P1.4_A4") (pintype "bidirectional"))
    )
    (net (code "222") (name "unconnected-(U$10-PadP1.5_A5)") (class "Default")
      (node (ref "U$10") (pin "P1.5_A5") (pinfunction "P1.5_A5_P1.5_A5") (pintype "bidirectional"))
    )
    (net (code "223") (name "unconnected-(U$10-PadP2.2_GPIO{slash}PWM)") (class "Default")
      (node (ref "U$10") (pin "P2.2_GPIO/PWM") (pinfunction "P2.2_GPIO/PWM_P2.2_GPIO/PWM") (pintype "bidirectional"))
    )
    (net (code "224") (name "unconnected-(U$10-PadP2.7_SPI-CS3)") (class "Default")
      (node (ref "U$10") (pin "P2.7_SPI-CS3") (pinfunction "P2.7_SPI-CS3_P2.7_SPI-CS3") (pintype "bidirectional"))
    )
    (net (code "225") (name "unconnected-(U$10-PadP3.0_A12)") (class "Default")
      (node (ref "U$10") (pin "P3.0_A12") (pinfunction "P3.0_A12_P3.0_A12") (pintype "bidirectional"))
    )
    (net (code "226") (name "unconnected-(U$10-PadP3.1_A13)") (class "Default")
      (node (ref "U$10") (pin "P3.1_A13") (pinfunction "P3.1_A13_P3.1_A13") (pintype "bidirectional"))
    )
    (net (code "227") (name "unconnected-(U$10-PadP3.2_A14)") (class "Default")
      (node (ref "U$10") (pin "P3.2_A14") (pinfunction "P3.2_A14_P3.2_A14") (pintype "bidirectional"))
    )
    (net (code "228") (name "unconnected-(U$10-PadP3.3_A15)") (class "Default")
      (node (ref "U$10") (pin "P3.3_A15") (pinfunction "P3.3_A15_P3.3_A15") (pintype "bidirectional"))
    )
    (net (code "229") (name "unconnected-(U$10-PadP4.1_GPIO)") (class "Default")
      (node (ref "U$10") (pin "P4.1_GPIO") (pinfunction "P4.1_GPIO_P4.1_GPIO") (pintype "bidirectional"))
    )
    (net (code "230") (name "unconnected-(U$10-PadP4.2_GPIO)") (class "Default")
      (node (ref "U$10") (pin "P4.2_GPIO") (pinfunction "P4.2_GPIO_P4.2_GPIO") (pintype "bidirectional"))
    )
    (net (code "231") (name "unconnected-(U$10-PadP5.0_I2C-SDA-1)") (class "Default")
      (node (ref "U$10") (pin "P5.0_I2C-SDA-1") (pinfunction "P5.0_I2C-SDA-1_P5.0_I2C-SDA-1") (pintype "bidirectional"))
    )
    (net (code "232") (name "unconnected-(U$10-PadP5.1_I2C-SCL-1)") (class "Default")
      (node (ref "U$10") (pin "P5.1_I2C-SCL-1") (pinfunction "P5.1_I2C-SCL-1_P5.1_I2C-SCL-1") (pintype "bidirectional"))
    )
    (net (code "233") (name "unconnected-(U$10-PadP5.4_SPI-MOSI)") (class "Default")
      (node (ref "U$10") (pin "P5.4_SPI-MOSI") (pinfunction "P5.4_SPI-MOSI_P5.4_SPI-MOSI") (pintype "bidirectional"))
    )
    (net (code "234") (name "unconnected-(U$10-PadP5.5_SPI-MISO)") (class "Default")
      (node (ref "U$10") (pin "P5.5_SPI-MISO") (pinfunction "P5.5_SPI-MISO_P5.5_SPI-MISO") (pintype "bidirectional"))
    )
    (net (code "235") (name "unconnected-(U$10-PadP5.6_SPI-CLK)") (class "Default")
      (node (ref "U$10") (pin "P5.6_SPI-CLK") (pinfunction "P5.6_SPI-CLK_P5.6_SPI-CLK") (pintype "bidirectional"))
    )
    (net (code "236") (name "unconnected-(U$10-PadP7.0_I2C-SDA-2)") (class "Default")
      (node (ref "U$10") (pin "P7.0_I2C-SDA-2") (pinfunction "P7.0_I2C-SDA-2_P7.0_I2C-SDA-2") (pintype "bidirectional"))
    )
    (net (code "237") (name "unconnected-(U$10-PadP7.1_I2C-SCL-2)") (class "Default")
      (node (ref "U$10") (pin "P7.1_I2C-SCL-2") (pinfunction "P7.1_I2C-SCL-2_P7.1_I2C-SCL-2") (pintype "bidirectional"))
    )
    (net (code "238") (name "unconnected-(U$13-P2.3_SPI-CS2-PadP2.4_SPI-CS2)") (class "Default")
      (node (ref "U$13") (pin "P2.4_SPI-CS2") (pinfunction "P2.3_SPI-CS2_P2.4_SPI-CS2") (pintype "bidirectional"))
    )
    (net (code "239") (name "unconnected-(U$13-PadP1.0_A0)") (class "Default")
      (node (ref "U$13") (pin "P1.0_A0") (pinfunction "P1.0_A0_P1.0_A0") (pintype "bidirectional"))
    )
    (net (code "240") (name "unconnected-(U$13-PadP1.1_A1)") (class "Default")
      (node (ref "U$13") (pin "P1.1_A1") (pinfunction "P1.1_A1_P1.1_A1") (pintype "bidirectional"))
    )
    (net (code "241") (name "unconnected-(U$13-PadP1.2_A2)") (class "Default")
      (node (ref "U$13") (pin "P1.2_A2") (pinfunction "P1.2_A2_P1.2_A2") (pintype "bidirectional"))
    )
    (net (code "242") (name "unconnected-(U$13-PadP1.3_A3)") (class "Default")
      (node (ref "U$13") (pin "P1.3_A3") (pinfunction "P1.3_A3_P1.3_A3") (pintype "bidirectional"))
    )
    (net (code "243") (name "unconnected-(U$13-PadP1.4_A4)") (class "Default")
      (node (ref "U$13") (pin "P1.4_A4") (pinfunction "P1.4_A4_P1.4_A4") (pintype "bidirectional"))
    )
    (net (code "244") (name "unconnected-(U$13-PadP1.5_A5)") (class "Default")
      (node (ref "U$13") (pin "P1.5_A5") (pinfunction "P1.5_A5_P1.5_A5") (pintype "bidirectional"))
    )
    (net (code "245") (name "unconnected-(U$13-PadP2.2_GPIO{slash}PWM)") (class "Default")
      (node (ref "U$13") (pin "P2.2_GPIO/PWM") (pinfunction "P2.2_GPIO/PWM_P2.2_GPIO/PWM") (pintype "bidirectional"))
    )
    (net (code "246") (name "unconnected-(U$13-PadP2.7_SPI-CS3)") (class "Default")
      (node (ref "U$13") (pin "P2.7_SPI-CS3") (pinfunction "P2.7_SPI-CS3_P2.7_SPI-CS3") (pintype "bidirectional"))
    )
    (net (code "247") (name "unconnected-(U$13-PadP3.0_A12)") (class "Default")
      (node (ref "U$13") (pin "P3.0_A12") (pinfunction "P3.0_A12_P3.0_A12") (pintype "bidirectional"))
    )
    (net (code "248") (name "unconnected-(U$13-PadP3.1_A13)") (class "Default")
      (node (ref "U$13") (pin "P3.1_A13") (pinfunction "P3.1_A13_P3.1_A13") (pintype "bidirectional"))
    )
    (net (code "249") (name "unconnected-(U$13-PadP3.2_A14)") (class "Default")
      (node (ref "U$13") (pin "P3.2_A14") (pinfunction "P3.2_A14_P3.2_A14") (pintype "bidirectional"))
    )
    (net (code "250") (name "unconnected-(U$13-PadP3.3_A15)") (class "Default")
      (node (ref "U$13") (pin "P3.3_A15") (pinfunction "P3.3_A15_P3.3_A15") (pintype "bidirectional"))
    )
    (net (code "251") (name "unconnected-(U$13-PadP4.1_GPIO)") (class "Default")
      (node (ref "U$13") (pin "P4.1_GPIO") (pinfunction "P4.1_GPIO_P4.1_GPIO") (pintype "bidirectional"))
    )
    (net (code "252") (name "unconnected-(U$13-PadP4.2_GPIO)") (class "Default")
      (node (ref "U$13") (pin "P4.2_GPIO") (pinfunction "P4.2_GPIO_P4.2_GPIO") (pintype "bidirectional"))
    )
    (net (code "253") (name "unconnected-(U$13-PadP5.0_I2C-SDA-1)") (class "Default")
      (node (ref "U$13") (pin "P5.0_I2C-SDA-1") (pinfunction "P5.0_I2C-SDA-1_P5.0_I2C-SDA-1") (pintype "bidirectional"))
    )
    (net (code "254") (name "unconnected-(U$13-PadP5.1_I2C-SCL-1)") (class "Default")
      (node (ref "U$13") (pin "P5.1_I2C-SCL-1") (pinfunction "P5.1_I2C-SCL-1_P5.1_I2C-SCL-1") (pintype "bidirectional"))
    )
    (net (code "255") (name "unconnected-(U$13-PadP5.4_SPI-MOSI)") (class "Default")
      (node (ref "U$13") (pin "P5.4_SPI-MOSI") (pinfunction "P5.4_SPI-MOSI_P5.4_SPI-MOSI") (pintype "bidirectional"))
    )
    (net (code "256") (name "unconnected-(U$13-PadP5.5_SPI-MISO)") (class "Default")
      (node (ref "U$13") (pin "P5.5_SPI-MISO") (pinfunction "P5.5_SPI-MISO_P5.5_SPI-MISO") (pintype "bidirectional"))
    )
    (net (code "257") (name "unconnected-(U$13-PadP5.6_SPI-CLK)") (class "Default")
      (node (ref "U$13") (pin "P5.6_SPI-CLK") (pinfunction "P5.6_SPI-CLK_P5.6_SPI-CLK") (pintype "bidirectional"))
    )
    (net (code "258") (name "unconnected-(U$13-PadP7.0_I2C-SDA-2)") (class "Default")
      (node (ref "U$13") (pin "P7.0_I2C-SDA-2") (pinfunction "P7.0_I2C-SDA-2_P7.0_I2C-SDA-2") (pintype "bidirectional"))
    )
    (net (code "259") (name "unconnected-(U$13-PadP7.1_I2C-SCL-2)") (class "Default")
      (node (ref "U$13") (pin "P7.1_I2C-SCL-2") (pinfunction "P7.1_I2C-SCL-2_P7.1_I2C-SCL-2") (pintype "bidirectional"))
    )
  )
)
